# EA08AI-V1.net
KiCad netlist of a schematic drawn in Altium Designer
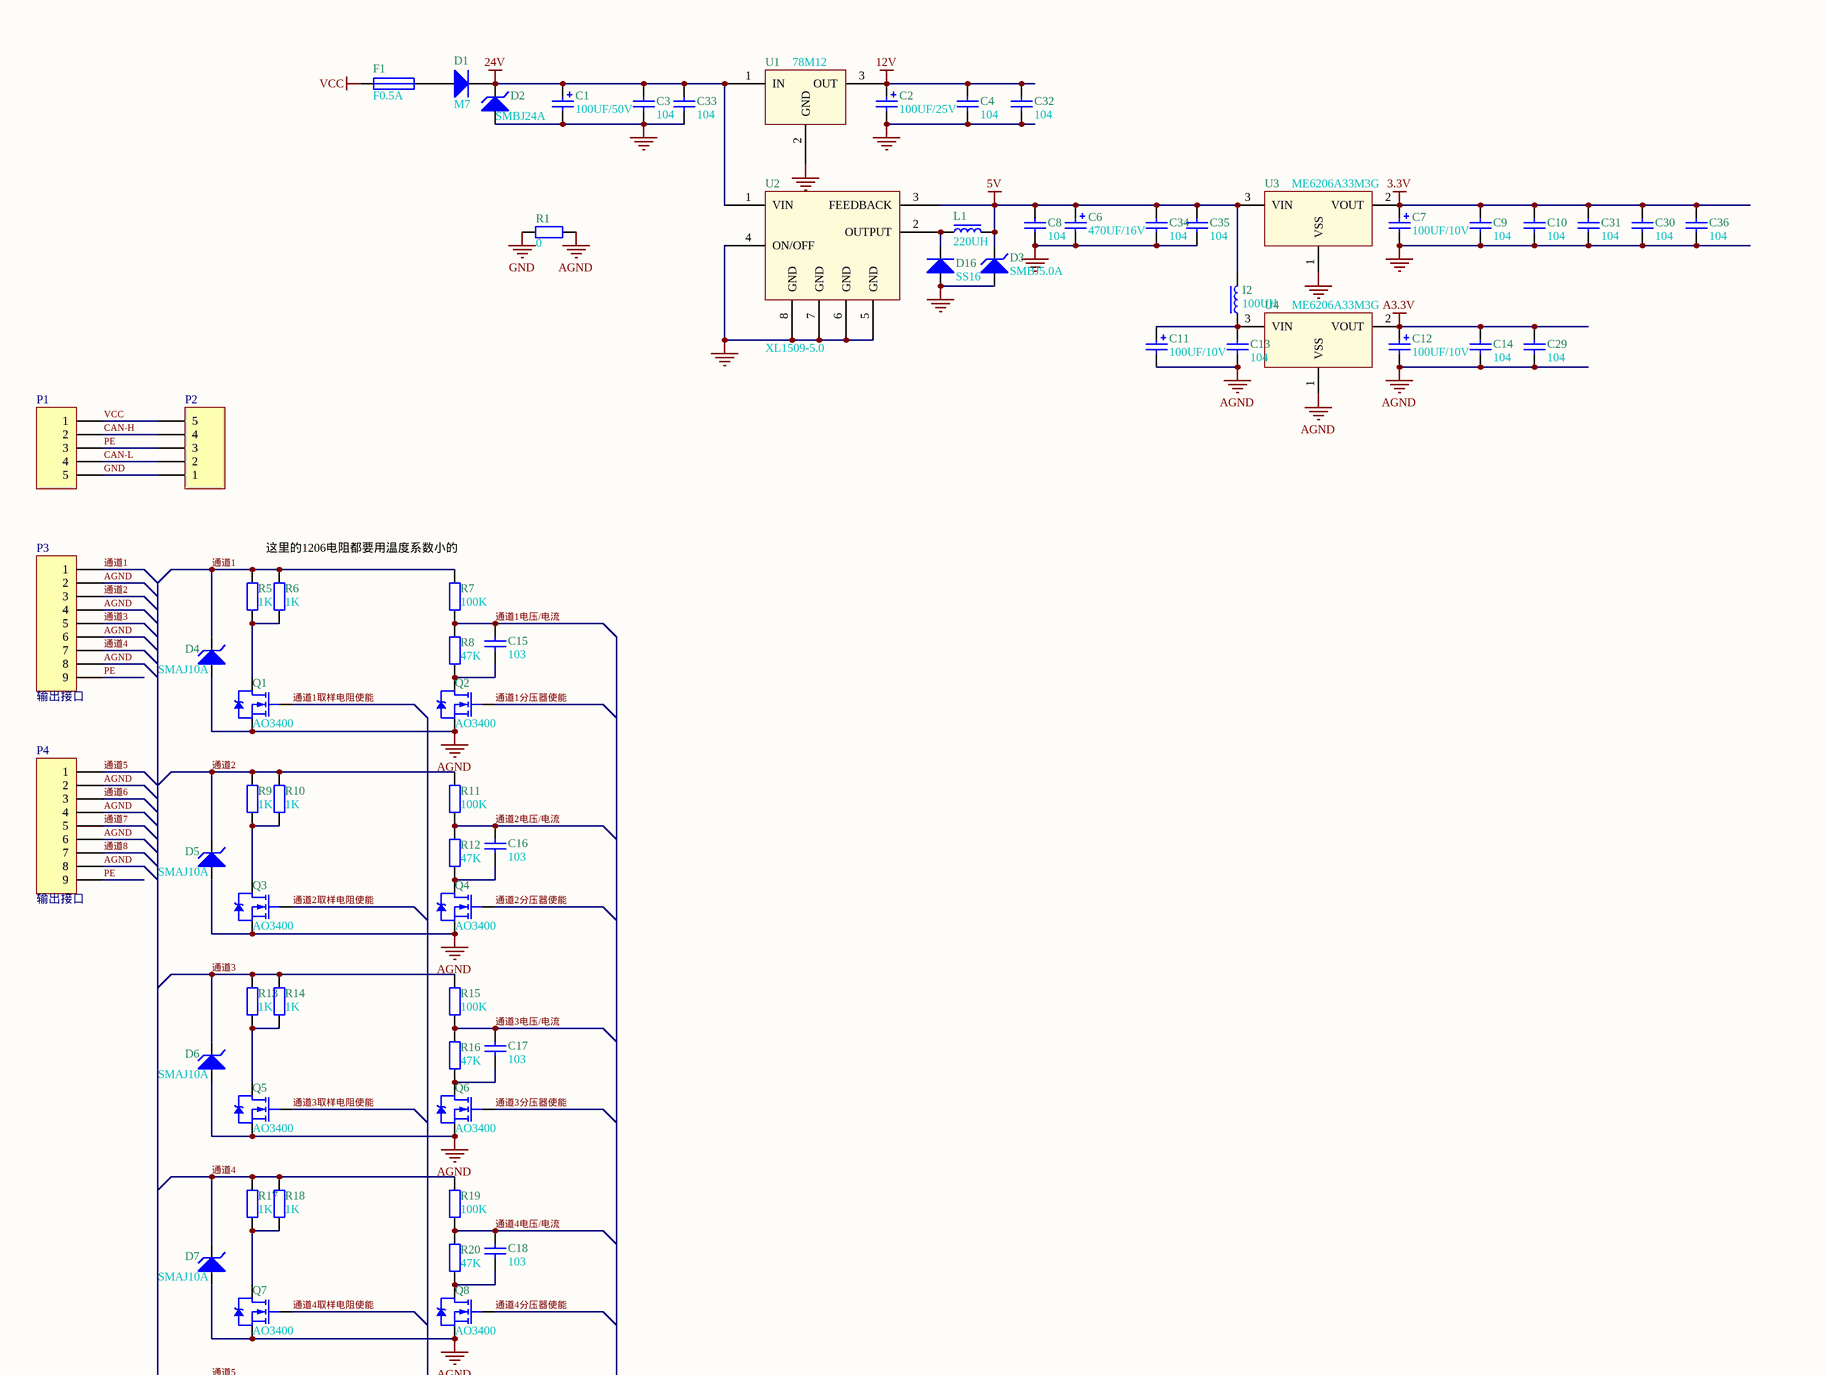
[diagram p0: EA08AI-V1.SchDoc, top]
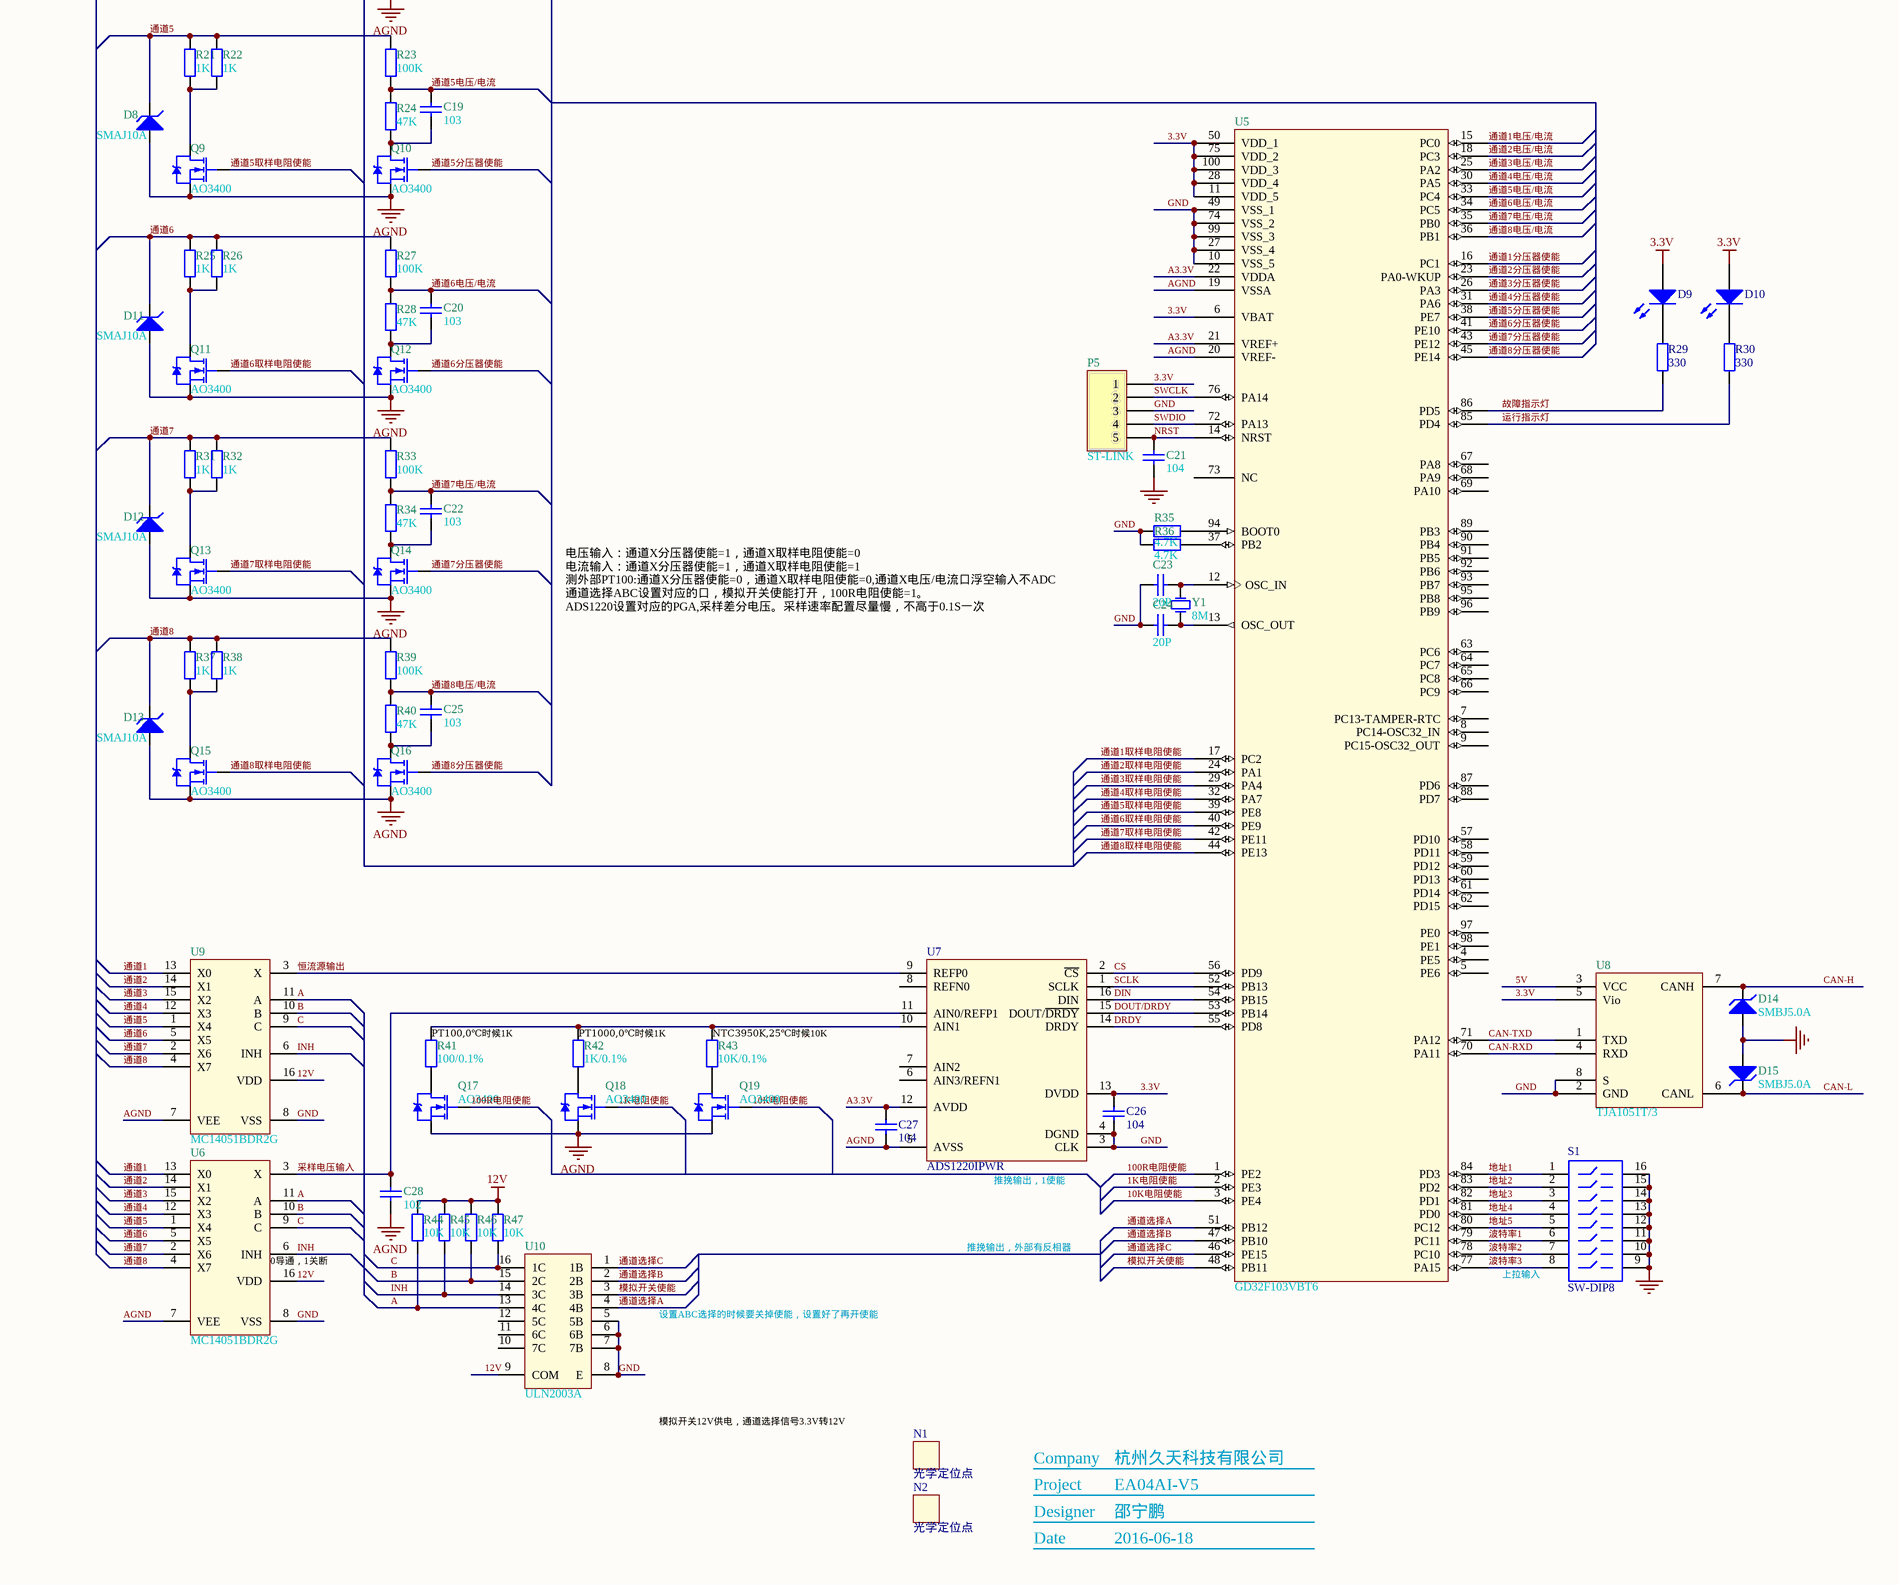
[diagram p1: EA08AI-V1.SchDoc, bottom]

(export (version "E")
  (design (tool "Eeschema 10.0.6"))
  (components
    (comp (ref "C1")
      (value "100UF/50V")
      (footprint "贴片固态电容8*10-M")
      (description "Polarized Capacitor (Radial)")
      (fields (field (name "PUBLISHER") "Altium Limited"))
      (libsource (lib "元件2.0") (part "Cap Pol1"))
    )
    (comp (ref "C2")
      (value "100UF/25V")
      (footprint "贴片固态电容5*5.3")
      (description "Polarized Capacitor (Radial)")
      (fields (field (name "PUBLISHER") "Altium Limited"))
      (libsource (lib "元件2.0") (part "Cap Pol1"))
    )
    (comp (ref "C3")
      (value "104")
      (footprint "C-0603")
      (description "Capacitor")
      (fields (field (name "PUBLISHER") "Altium Limited"))
      (libsource (lib "元件2.0") (part "Cap"))
    )
    (comp (ref "C4")
      (value "104")
      (footprint "C-0603")
      (description "Capacitor")
      (fields (field (name "PUBLISHER") "Altium Limited"))
      (libsource (lib "元件2.0") (part "Cap"))
    )
    (comp (ref "C6")
      (value "470UF/16V")
      (footprint "贴片固态电容8*10-M")
      (description "Polarized Capacitor (Radial)")
      (fields (field (name "PUBLISHER") "Altium Limited"))
      (libsource (lib "元件2.0") (part "Cap Pol1"))
    )
    (comp (ref "C7")
      (value "100UF/10V")
      (footprint "贴片固态电容5*5.3")
      (description "Polarized Capacitor (Radial)")
      (fields (field (name "PUBLISHER") "Altium Limited"))
      (libsource (lib "元件2.0") (part "Cap Pol1"))
    )
    (comp (ref "C8")
      (value "104")
      (footprint "C-0603")
      (description "Capacitor")
      (fields (field (name "PUBLISHER") "Altium Limited"))
      (libsource (lib "元件2.0") (part "Cap"))
    )
    (comp (ref "C9")
      (value "104")
      (footprint "C-0603")
      (description "Capacitor")
      (fields (field (name "PUBLISHER") "Altium Limited"))
      (libsource (lib "元件2.0") (part "Cap"))
    )
    (comp (ref "C10")
      (value "104")
      (footprint "C-0603")
      (description "Capacitor")
      (fields (field (name "PUBLISHER") "Altium Limited"))
      (libsource (lib "元件2.0") (part "Cap"))
    )
    (comp (ref "C11")
      (value "100UF/10V")
      (footprint "贴片固态电容5*5.3")
      (description "Polarized Capacitor (Radial)")
      (fields (field (name "PUBLISHER") "Altium Limited"))
      (libsource (lib "元件2.0") (part "Cap Pol1"))
    )
    (comp (ref "C12")
      (value "100UF/10V")
      (footprint "贴片固态电容5*5.3")
      (description "Polarized Capacitor (Radial)")
      (fields (field (name "PUBLISHER") "Altium Limited"))
      (libsource (lib "元件2.0") (part "Cap Pol1"))
    )
    (comp (ref "C13")
      (value "104")
      (footprint "C-0603")
      (description "Capacitor")
      (fields (field (name "PUBLISHER") "Altium Limited"))
      (libsource (lib "元件2.0") (part "Cap"))
    )
    (comp (ref "C14")
      (value "104")
      (footprint "C-0603")
      (description "Capacitor")
      (fields (field (name "PUBLISHER") "Altium Limited"))
      (libsource (lib "元件2.0") (part "Cap"))
    )
    (comp (ref "C15")
      (value "103")
      (footprint "C-0603")
      (description "0805")
      (fields (field (name "PUBLISHER") "Altium Limited"))
      (libsource (lib "2电容-V1.0") (part "Cap-0603"))
    )
    (comp (ref "C16")
      (value "103")
      (footprint "C-0603")
      (description "0805")
      (fields (field (name "PUBLISHER") "Altium Limited"))
      (libsource (lib "2电容-V1.0") (part "Cap-0603"))
    )
    (comp (ref "C17")
      (value "103")
      (footprint "C-0603")
      (description "0805")
      (fields (field (name "PUBLISHER") "Altium Limited"))
      (libsource (lib "2电容-V1.0") (part "Cap-0603"))
    )
    (comp (ref "C18")
      (value "103")
      (footprint "C-0603")
      (description "0805")
      (fields (field (name "PUBLISHER") "Altium Limited"))
      (libsource (lib "2电容-V1.0") (part "Cap-0603"))
    )
    (comp (ref "C19")
      (value "103")
      (footprint "C-0603")
      (description "0805")
      (fields (field (name "PUBLISHER") "Altium Limited"))
      (libsource (lib "2电容-V1.0") (part "Cap-0603"))
    )
    (comp (ref "C20")
      (value "103")
      (footprint "C-0603")
      (description "0805")
      (fields (field (name "PUBLISHER") "Altium Limited"))
      (libsource (lib "2电容-V1.0") (part "Cap-0603"))
    )
    (comp (ref "C21")
      (value "104")
      (footprint "C-0603")
      (description "Capacitor")
      (fields (field (name "PUBLISHER") "Altium Limited"))
      (libsource (lib "元件2.0") (part "Cap"))
    )
    (comp (ref "C22")
      (value "103")
      (footprint "C-0603")
      (description "0805")
      (fields (field (name "PUBLISHER") "Altium Limited"))
      (libsource (lib "2电容-V1.0") (part "Cap-0603"))
    )
    (comp (ref "C23")
      (value "20P")
      (footprint "C-0603")
      (description "0805")
      (fields (field (name "PUBLISHER") "Altium Limited"))
      (libsource (lib "2电容-V1.0") (part "Cap-0603"))
    )
    (comp (ref "C24")
      (value "20P")
      (footprint "C-0603")
      (description "0805")
      (fields (field (name "PUBLISHER") "Altium Limited"))
      (libsource (lib "2电容-V1.0") (part "Cap-0603"))
    )
    (comp (ref "C25")
      (value "103")
      (footprint "C-0603")
      (description "0805")
      (fields (field (name "PUBLISHER") "Altium Limited"))
      (libsource (lib "2电容-V1.0") (part "Cap-0603"))
    )
    (comp (ref "C26")
      (value "104")
      (footprint "C-0603")
      (description "0805")
      (fields (field (name "PUBLISHER") "Altium Limited"))
      (libsource (lib "2电容-V1.0") (part "Cap-0603"))
    )
    (comp (ref "C27")
      (value "104")
      (footprint "C-0603")
      (description "0805")
      (fields (field (name "PUBLISHER") "Altium Limited"))
      (libsource (lib "2电容-V1.0") (part "Cap-0603"))
    )
    (comp (ref "C28")
      (value "102")
      (footprint "C-0603")
      (description "Capacitor")
      (fields (field (name "PUBLISHER") "Altium Limited"))
      (libsource (lib "元件2.0") (part "Cap"))
    )
    (comp (ref "C29")
      (value "104")
      (footprint "C-0603")
      (description "Capacitor")
      (fields (field (name "PUBLISHER") "Altium Limited"))
      (libsource (lib "元件2.0") (part "Cap"))
    )
    (comp (ref "C30")
      (value "104")
      (footprint "C-0603")
      (description "Capacitor")
      (fields (field (name "PUBLISHER") "Altium Limited"))
      (libsource (lib "元件2.0") (part "Cap"))
    )
    (comp (ref "C31")
      (value "104")
      (footprint "C-0603")
      (description "Capacitor")
      (fields (field (name "PUBLISHER") "Altium Limited"))
      (libsource (lib "元件2.0") (part "Cap"))
    )
    (comp (ref "C32")
      (value "104")
      (footprint "C-0603")
      (description "Capacitor")
      (fields (field (name "PUBLISHER") "Altium Limited"))
      (libsource (lib "元件2.0") (part "Cap"))
    )
    (comp (ref "C33")
      (value "104")
      (footprint "C-0603")
      (description "Capacitor")
      (fields (field (name "PUBLISHER") "Altium Limited"))
      (libsource (lib "元件2.0") (part "Cap"))
    )
    (comp (ref "C34")
      (value "104")
      (footprint "C-0603")
      (description "Capacitor")
      (fields (field (name "PUBLISHER") "Altium Limited"))
      (libsource (lib "元件2.0") (part "Cap"))
    )
    (comp (ref "C35")
      (value "104")
      (footprint "C-0603")
      (description "Capacitor")
      (fields (field (name "PUBLISHER") "Altium Limited"))
      (libsource (lib "元件2.0") (part "Cap"))
    )
    (comp (ref "C36")
      (value "104")
      (footprint "C-0603")
      (description "Capacitor")
      (fields (field (name "PUBLISHER") "Altium Limited"))
      (libsource (lib "元件2.0") (part "Cap"))
    )
    (comp (ref "D1")
      (value "M7")
      (footprint "SMA")
      (description "SMA")
      (fields (field (name "PUBLISHER") "Altium Limited"))
      (libsource (lib "4二极管-V1.1") (part "M7"))
    )
    (comp (ref "D2")
      (value "SMBJ24A")
      (footprint "SMB")
      (description "SMB")
      (libsource (lib "4二极管-V1.1") (part "TVS-1"))
    )
    (comp (ref "D3")
      (value "SMBJ5.0A")
      (footprint "SMB")
      (description "SMB")
      (libsource (lib "4二极管-V1.1") (part "TVS-1"))
    )
    (comp (ref "D4")
      (value "SMAJ10A")
      (footprint "SMA")
      (description "SMB")
      (libsource (lib "4二极管-V1.1") (part "TVS-1"))
    )
    (comp (ref "D5")
      (value "SMAJ10A")
      (footprint "SMA")
      (description "SMB")
      (libsource (lib "4二极管-V1.1") (part "TVS-1"))
    )
    (comp (ref "D6")
      (value "SMAJ10A")
      (footprint "SMA")
      (description "SMB")
      (libsource (lib "4二极管-V1.1") (part "TVS-1"))
    )
    (comp (ref "D7")
      (value "SMAJ10A")
      (footprint "SMA")
      (description "SMB")
      (libsource (lib "4二极管-V1.1") (part "TVS-1"))
    )
    (comp (ref "D8")
      (value "SMAJ10A")
      (footprint "SMA")
      (description "SMB")
      (libsource (lib "4二极管-V1.1") (part "TVS-1"))
    )
    (comp (ref "D9")
      (value "~")
      (footprint "LED Φ3红2.54mm")
      (fields (field (name "PUBLISHER") "Altium Limited"))
      (libsource (lib "4二极管-V1.1") (part "LED-0603-Blue"))
    )
    (comp (ref "D10")
      (value "~")
      (footprint "LED Φ3绿2.54mm")
      (fields (field (name "PUBLISHER") "Altium Limited"))
      (libsource (lib "4二极管-V1.1") (part "LED-0603-Blue"))
    )
    (comp (ref "D11")
      (value "SMAJ10A")
      (footprint "SMA")
      (description "SMB")
      (libsource (lib "4二极管-V1.1") (part "TVS-1"))
    )
    (comp (ref "D12")
      (value "SMAJ10A")
      (footprint "SMA")
      (description "SMB")
      (libsource (lib "4二极管-V1.1") (part "TVS-1"))
    )
    (comp (ref "D13")
      (value "SMAJ10A")
      (footprint "SMA")
      (description "SMB")
      (libsource (lib "4二极管-V1.1") (part "TVS-1"))
    )
    (comp (ref "D14")
      (value "SMBJ5.0A")
      (footprint "SMB")
      (description "SMB")
      (libsource (lib "4二极管-V1.1") (part "TVS-1"))
    )
    (comp (ref "D15")
      (value "SMBJ5.0A")
      (footprint "SMB")
      (description "SMB")
      (libsource (lib "4二极管-V1.1") (part "TVS-1"))
    )
    (comp (ref "D16")
      (value "SS16")
      (footprint "SMA")
      (description "SMA")
      (libsource (lib "4二极管-V1.1") (part "SS14"))
    )
    (comp (ref "F1")
      (value "F0.5A")
      (footprint "FUSE-1808")
      (description "Fuse")
      (fields (field (name "PUBLISHER") "Altium Limited"))
      (libsource (lib "11其他元件-V1.0") (part "Fuse 1"))
    )
    (comp (ref "I2") (value "100UH") (footprint "CD54") (libsource (lib "3电感-V1.0") (part "Inductance3")))
    (comp (ref "L1") (value "220UH") (footprint "CD75") (libsource (lib "3电感-V1.0") (part "Inductance3")))
    (comp (ref "N1") (value "光学定位点") (footprint "MARK-1mm-3mm") (libsource (lib "11其他元件-V1.0") (part "无引脚")))
    (comp (ref "N2") (value "光学定位点") (footprint "MARK-1mm-3mm") (libsource (lib "11其他元件-V1.0") (part "无引脚")))
    (comp (ref "P1")
      (value "~")
      (footprint "弯针5.08-M-5P")
      (description "Header, 5-Pin")
      (fields (field (name "PUBLISHER") "Altium Limited"))
      (libsource (lib "5排针-V1.0") (part "Header 5"))
    )
    (comp (ref "P2")
      (value "~")
      (footprint "KF2EDGVC-5.08-5P弯针")
      (description "Header, 5-Pin")
      (fields (field (name "PUBLISHER") "Altium Limited"))
      (libsource (lib "") (part "Header 5_1"))
    )
    (comp (ref "P3")
      (value "输出接口")
      (footprint "KF2EDGVC-5.08-9P")
      (description "Header, 9-Pin")
      (fields (field (name "PUBLISHER") "Altium Limited"))
      (libsource (lib "5排针-V1.0") (part "Header 9"))
    )
    (comp (ref "P4")
      (value "输出接口")
      (footprint "KF2EDGVC-5.08-9P")
      (description "Header, 9-Pin")
      (fields (field (name "PUBLISHER") "Altium Limited"))
      (libsource (lib "5排针-V1.0") (part "Header 9"))
    )
    (comp (ref "P5")
      (value "ST-LINK")
      (footprint "5P下载口")
      (description "Header, 5-Pin")
      (fields (field (name "PUBLISHER") "Altium Limited"))
      (libsource (lib "5排针-V1.0") (part "Header 5"))
    )
    (comp (ref "Q1")
      (value "AO3400")
      (footprint "SOT-23")
      (description "SOT-23")
      (libsource (lib "4二极管-V1.1") (part "AO3400"))
    )
    (comp (ref "Q2")
      (value "AO3400")
      (footprint "SOT-23")
      (description "SOT-23")
      (libsource (lib "4二极管-V1.1") (part "AO3400"))
    )
    (comp (ref "Q3")
      (value "AO3400")
      (footprint "SOT-23")
      (description "SOT-23")
      (libsource (lib "4二极管-V1.1") (part "AO3400"))
    )
    (comp (ref "Q4")
      (value "AO3400")
      (footprint "SOT-23")
      (description "SOT-23")
      (libsource (lib "4二极管-V1.1") (part "AO3400"))
    )
    (comp (ref "Q5")
      (value "AO3400")
      (footprint "SOT-23")
      (description "SOT-23")
      (libsource (lib "4二极管-V1.1") (part "AO3400"))
    )
    (comp (ref "Q6")
      (value "AO3400")
      (footprint "SOT-23")
      (description "SOT-23")
      (libsource (lib "4二极管-V1.1") (part "AO3400"))
    )
    (comp (ref "Q7")
      (value "AO3400")
      (footprint "SOT-23")
      (description "SOT-23")
      (libsource (lib "4二极管-V1.1") (part "AO3400"))
    )
    (comp (ref "Q8")
      (value "AO3400")
      (footprint "SOT-23")
      (description "SOT-23")
      (libsource (lib "4二极管-V1.1") (part "AO3400"))
    )
    (comp (ref "Q9")
      (value "AO3400")
      (footprint "SOT-23")
      (description "SOT-23")
      (libsource (lib "4二极管-V1.1") (part "AO3400"))
    )
    (comp (ref "Q10")
      (value "AO3400")
      (footprint "SOT-23")
      (description "SOT-23")
      (libsource (lib "4二极管-V1.1") (part "AO3400"))
    )
    (comp (ref "Q11")
      (value "AO3400")
      (footprint "SOT-23")
      (description "SOT-23")
      (libsource (lib "4二极管-V1.1") (part "AO3400"))
    )
    (comp (ref "Q12")
      (value "AO3400")
      (footprint "SOT-23")
      (description "SOT-23")
      (libsource (lib "4二极管-V1.1") (part "AO3400"))
    )
    (comp (ref "Q13")
      (value "AO3400")
      (footprint "SOT-23")
      (description "SOT-23")
      (libsource (lib "4二极管-V1.1") (part "AO3400"))
    )
    (comp (ref "Q14")
      (value "AO3400")
      (footprint "SOT-23")
      (description "SOT-23")
      (libsource (lib "4二极管-V1.1") (part "AO3400"))
    )
    (comp (ref "Q15")
      (value "AO3400")
      (footprint "SOT-23")
      (description "SOT-23")
      (libsource (lib "4二极管-V1.1") (part "AO3400"))
    )
    (comp (ref "Q16")
      (value "AO3400")
      (footprint "SOT-23")
      (description "SOT-23")
      (libsource (lib "4二极管-V1.1") (part "AO3400"))
    )
    (comp (ref "Q17")
      (value "AO3400")
      (footprint "SOT-23")
      (description "SOT-23")
      (libsource (lib "4二极管-V1.1") (part "AO3400"))
    )
    (comp (ref "Q18")
      (value "AO3400")
      (footprint "SOT-23")
      (description "SOT-23")
      (libsource (lib "4二极管-V1.1") (part "AO3400"))
    )
    (comp (ref "Q19")
      (value "AO3400")
      (footprint "SOT-23")
      (description "SOT-23")
      (libsource (lib "4二极管-V1.1") (part "AO3400"))
    )
    (comp (ref "R1")
      (value "0")
      (footprint "R-1206")
      (description "0603")
      (fields (field (name "PUBLISHER") "Altium Limited"))
      (libsource (lib "") (part "Res2-0603_1"))
    )
    (comp (ref "R5")
      (value "1K")
      (footprint "R-1206")
      (description "0603")
      (fields (field (name "PUBLISHER") "Altium Limited"))
      (libsource (lib "") (part "Res2-0603_1"))
    )
    (comp (ref "R6")
      (value "1K")
      (footprint "R-1206")
      (description "0603")
      (fields (field (name "PUBLISHER") "Altium Limited"))
      (libsource (lib "") (part "Res2-0603_1"))
    )
    (comp (ref "R7")
      (value "100K")
      (footprint "R-1206")
      (description "0603")
      (fields (field (name "PUBLISHER") "Altium Limited"))
      (libsource (lib "") (part "Res2-0603_1"))
    )
    (comp (ref "R8")
      (value "47K")
      (footprint "R-1206")
      (description "0603")
      (fields (field (name "PUBLISHER") "Altium Limited"))
      (libsource (lib "") (part "Res2-0603_1"))
    )
    (comp (ref "R9")
      (value "1K")
      (footprint "R-1206")
      (description "0603")
      (fields (field (name "PUBLISHER") "Altium Limited"))
      (libsource (lib "") (part "Res2-0603_1"))
    )
    (comp (ref "R10")
      (value "1K")
      (footprint "R-1206")
      (description "0603")
      (fields (field (name "PUBLISHER") "Altium Limited"))
      (libsource (lib "") (part "Res2-0603_1"))
    )
    (comp (ref "R11")
      (value "100K")
      (footprint "R-1206")
      (description "0603")
      (fields (field (name "PUBLISHER") "Altium Limited"))
      (libsource (lib "") (part "Res2-0603_1"))
    )
    (comp (ref "R12")
      (value "47K")
      (footprint "R-1206")
      (description "0603")
      (fields (field (name "PUBLISHER") "Altium Limited"))
      (libsource (lib "") (part "Res2-0603_1"))
    )
    (comp (ref "R13")
      (value "1K")
      (footprint "R-1206")
      (description "0603")
      (fields (field (name "PUBLISHER") "Altium Limited"))
      (libsource (lib "") (part "Res2-0603_1"))
    )
    (comp (ref "R14")
      (value "1K")
      (footprint "R-1206")
      (description "0603")
      (fields (field (name "PUBLISHER") "Altium Limited"))
      (libsource (lib "") (part "Res2-0603_1"))
    )
    (comp (ref "R15")
      (value "100K")
      (footprint "R-1206")
      (description "0603")
      (fields (field (name "PUBLISHER") "Altium Limited"))
      (libsource (lib "") (part "Res2-0603_1"))
    )
    (comp (ref "R16")
      (value "47K")
      (footprint "R-1206")
      (description "0603")
      (fields (field (name "PUBLISHER") "Altium Limited"))
      (libsource (lib "") (part "Res2-0603_1"))
    )
    (comp (ref "R17")
      (value "1K")
      (footprint "R-1206")
      (description "0603")
      (fields (field (name "PUBLISHER") "Altium Limited"))
      (libsource (lib "") (part "Res2-0603_1"))
    )
    (comp (ref "R18")
      (value "1K")
      (footprint "R-1206")
      (description "0603")
      (fields (field (name "PUBLISHER") "Altium Limited"))
      (libsource (lib "") (part "Res2-0603_1"))
    )
    (comp (ref "R19")
      (value "100K")
      (footprint "R-1206")
      (description "0603")
      (fields (field (name "PUBLISHER") "Altium Limited"))
      (libsource (lib "") (part "Res2-0603_1"))
    )
    (comp (ref "R20")
      (value "47K")
      (footprint "R-1206")
      (description "0603")
      (fields (field (name "PUBLISHER") "Altium Limited"))
      (libsource (lib "") (part "Res2-0603_1"))
    )
    (comp (ref "R21")
      (value "1K")
      (footprint "R-1206")
      (description "0603")
      (fields (field (name "PUBLISHER") "Altium Limited"))
      (libsource (lib "") (part "Res2-0603_1"))
    )
    (comp (ref "R22")
      (value "1K")
      (footprint "R-1206")
      (description "0603")
      (fields (field (name "PUBLISHER") "Altium Limited"))
      (libsource (lib "") (part "Res2-0603_1"))
    )
    (comp (ref "R23")
      (value "100K")
      (footprint "R-1206")
      (description "0603")
      (fields (field (name "PUBLISHER") "Altium Limited"))
      (libsource (lib "") (part "Res2-0603_1"))
    )
    (comp (ref "R24")
      (value "47K")
      (footprint "R-1206")
      (description "0603")
      (fields (field (name "PUBLISHER") "Altium Limited"))
      (libsource (lib "") (part "Res2-0603_1"))
    )
    (comp (ref "R25")
      (value "1K")
      (footprint "R-1206")
      (description "0603")
      (fields (field (name "PUBLISHER") "Altium Limited"))
      (libsource (lib "") (part "Res2-0603_1"))
    )
    (comp (ref "R26")
      (value "1K")
      (footprint "R-1206")
      (description "0603")
      (fields (field (name "PUBLISHER") "Altium Limited"))
      (libsource (lib "") (part "Res2-0603_1"))
    )
    (comp (ref "R27")
      (value "100K")
      (footprint "R-1206")
      (description "0603")
      (fields (field (name "PUBLISHER") "Altium Limited"))
      (libsource (lib "") (part "Res2-0603_1"))
    )
    (comp (ref "R28")
      (value "47K")
      (footprint "R-1206")
      (description "0603")
      (fields (field (name "PUBLISHER") "Altium Limited"))
      (libsource (lib "") (part "Res2-0603_1"))
    )
    (comp (ref "R29")
      (value "330")
      (footprint "R-0603")
      (description "0603")
      (fields (field (name "PUBLISHER") "Altium Limited"))
      (libsource (lib "1电阻-V1.0") (part "Res2-0603"))
    )
    (comp (ref "R30")
      (value "330")
      (footprint "R-0603")
      (description "0603")
      (fields (field (name "PUBLISHER") "Altium Limited"))
      (libsource (lib "1电阻-V1.0") (part "Res2-0603"))
    )
    (comp (ref "R31")
      (value "1K")
      (footprint "R-1206")
      (description "0603")
      (fields (field (name "PUBLISHER") "Altium Limited"))
      (libsource (lib "") (part "Res2-0603_1"))
    )
    (comp (ref "R32")
      (value "1K")
      (footprint "R-1206")
      (description "0603")
      (fields (field (name "PUBLISHER") "Altium Limited"))
      (libsource (lib "") (part "Res2-0603_1"))
    )
    (comp (ref "R33")
      (value "100K")
      (footprint "R-1206")
      (description "0603")
      (fields (field (name "PUBLISHER") "Altium Limited"))
      (libsource (lib "") (part "Res2-0603_1"))
    )
    (comp (ref "R34")
      (value "47K")
      (footprint "R-1206")
      (description "0603")
      (fields (field (name "PUBLISHER") "Altium Limited"))
      (libsource (lib "") (part "Res2-0603_1"))
    )
    (comp (ref "R35")
      (value "4.7K")
      (footprint "R-0603")
      (description "0603")
      (fields (field (name "PUBLISHER") "Altium Limited"))
      (libsource (lib "") (part "Res2-0603_2"))
    )
    (comp (ref "R36")
      (value "4.7K")
      (footprint "R-0603")
      (description "0603")
      (fields (field (name "PUBLISHER") "Altium Limited"))
      (libsource (lib "") (part "Res2-0603_2"))
    )
    (comp (ref "R37")
      (value "1K")
      (footprint "R-1206")
      (description "0603")
      (fields (field (name "PUBLISHER") "Altium Limited"))
      (libsource (lib "") (part "Res2-0603_1"))
    )
    (comp (ref "R38")
      (value "1K")
      (footprint "R-1206")
      (description "0603")
      (fields (field (name "PUBLISHER") "Altium Limited"))
      (libsource (lib "") (part "Res2-0603_1"))
    )
    (comp (ref "R39")
      (value "100K")
      (footprint "R-1206")
      (description "0603")
      (fields (field (name "PUBLISHER") "Altium Limited"))
      (libsource (lib "") (part "Res2-0603_1"))
    )
    (comp (ref "R40")
      (value "47K")
      (footprint "R-1206")
      (description "0603")
      (fields (field (name "PUBLISHER") "Altium Limited"))
      (libsource (lib "") (part "Res2-0603_1"))
    )
    (comp (ref "R41")
      (value "100/0.1%")
      (footprint "R-1206")
      (description "0603")
      (fields (field (name "PUBLISHER") "Altium Limited"))
      (libsource (lib "") (part "Res2-0603_1"))
    )
    (comp (ref "R42")
      (value "1K/0.1%")
      (footprint "R-1206")
      (description "0603")
      (fields (field (name "PUBLISHER") "Altium Limited"))
      (libsource (lib "") (part "Res2-0603_1"))
    )
    (comp (ref "R43")
      (value "10K/0.1%")
      (footprint "R-1206")
      (description "0603")
      (fields (field (name "PUBLISHER") "Altium Limited"))
      (libsource (lib "") (part "Res2-0603_1"))
    )
    (comp (ref "R44")
      (value "10K")
      (footprint "R-0603")
      (description "0603")
      (fields (field (name "PUBLISHER") "Altium Limited"))
      (libsource (lib "1电阻-V1.0") (part "Res2-0603"))
    )
    (comp (ref "R45")
      (value "10K")
      (footprint "R-0603")
      (description "0603")
      (fields (field (name "PUBLISHER") "Altium Limited"))
      (libsource (lib "1电阻-V1.0") (part "Res2-0603"))
    )
    (comp (ref "R46")
      (value "10K")
      (footprint "R-0603")
      (description "0603")
      (fields (field (name "PUBLISHER") "Altium Limited"))
      (libsource (lib "1电阻-V1.0") (part "Res2-0603"))
    )
    (comp (ref "R47")
      (value "10K")
      (footprint "R-0603")
      (description "0603")
      (fields (field (name "PUBLISHER") "Altium Limited"))
      (libsource (lib "1电阻-V1.0") (part "Res2-0603"))
    )
    (comp (ref "S1")
      (value "SW-DIP8")
      (footprint "SW-蓝色拨码开关8P-加高")
      (fields (field (name "PUBLISHER") "Altium Limited"))
      (libsource (lib "开关-V1") (part "SW-DIP8"))
    )
    (comp (ref "U1")
      (value "78M12")
      (footprint "TO-252")
      (description "TO-252")
      (libsource (lib "电源芯片-线性稳压-V1") (part "78M05"))
    )
    (comp (ref "U2")
      (value "XL1509-5.0")
      (footprint "SOP-8-m")
      (description "开关电源 SOP-8")
      (libsource (lib "8集成电路-V1.1") (part "XL1509-ADJ"))
    )
    (comp (ref "U3")
      (value "ME6206A33M3G")
      (footprint "SOT-23")
      (description "LDO稳压 SOT-23")
      (libsource (lib "电源芯片-线性稳压-V1") (part "ME6206A33M3G"))
    )
    (comp (ref "U4")
      (value "ME6206A33M3G")
      (footprint "SOT-23")
      (description "LDO稳压 SOT-23")
      (libsource (lib "电源芯片-线性稳压-V1") (part "ME6206A33M3G"))
    )
    (comp (ref "U5")
      (value "GD32F103VBT6")
      (footprint "LQFP100")
      (libsource (lib "9单片机-V1.0") (part "GD32F103V"))
    )
    (comp (ref "U6")
      (value "MC14051BDR2G")
      (footprint "SOP-16-M")
      (libsource (lib "模拟开关") (part "MC14051BDR2G"))
    )
    (comp (ref "U7")
      (value "ADS1220IPWR")
      (footprint "TSSOP-16")
      (description "24位四通道ADC")
      (libsource (lib "ADC-DAC-V1") (part "ADS1220IPWR"))
    )
    (comp (ref "U8") (value "TJA1051T/3") (footprint "SOP-8-m") (libsource (lib "通讯-V1") (part "TJA1051T/3")))
    (comp (ref "U9")
      (value "MC14051BDR2G")
      (footprint "SOP-16-M")
      (libsource (lib "模拟开关") (part "MC14051BDR2G"))
    )
    (comp (ref "U10")
      (value "ULN2003A")
      (footprint "SOP-16-M")
      (libsource (lib "8集成电路-V1.1") (part "ULN2003A"))
    )
    (comp (ref "Y1") (value "8M") (footprint "HC-49SMD") (libsource (lib "11其他元件-V1.0") (part "晶振")))
  )
  (nets
    (net (code "1") (name "/1K电阻使能") (class "Default")
      (node (ref "Q18") (pin "1") (pinfunction "G_1") (pintype "passive"))
      (node (ref "U5") (pin "2") (pinfunction "PE3_2") (pintype "bidirectional"))
    )
    (net (code "2") (name "/10K电阻使能") (class "Default")
      (node (ref "Q19") (pin "1") (pinfunction "G_1") (pintype "passive"))
      (node (ref "U5") (pin "3") (pinfunction "PE4_3") (pintype "bidirectional"))
    )
    (net (code "3") (name "/100R电阻使能") (class "Default")
      (node (ref "Q17") (pin "1") (pinfunction "G_1") (pintype "passive"))
      (node (ref "U5") (pin "1") (pinfunction "PE2_1") (pintype "bidirectional"))
    )
    (net (code "4") (name "/A") (class "Default")
      (node (ref "R44") (pin "1") (pinfunction "1_1") (pintype "passive"))
      (node (ref "U10") (pin "13") (pinfunction "4C_13") (pintype "passive"))
      (node (ref "U6") (pin "11") (pinfunction "A_11") (pintype "passive"))
      (node (ref "U9") (pin "11") (pinfunction "A_11") (pintype "passive"))
    )
    (net (code "5") (name "/B") (class "Default")
      (node (ref "R46") (pin "1") (pinfunction "1_1") (pintype "passive"))
      (node (ref "U10") (pin "15") (pinfunction "2C_15") (pintype "passive"))
      (node (ref "U6") (pin "10") (pinfunction "B_10") (pintype "passive"))
      (node (ref "U9") (pin "10") (pinfunction "B_10") (pintype "passive"))
    )
    (net (code "6") (name "/C") (class "Default")
      (node (ref "R47") (pin "1") (pinfunction "1_1") (pintype "passive"))
      (node (ref "U10") (pin "16") (pinfunction "1C_16") (pintype "passive"))
      (node (ref "U6") (pin "9") (pinfunction "C_9") (pintype "passive"))
      (node (ref "U9") (pin "9") (pinfunction "C_9") (pintype "passive"))
    )
    (net (code "7") (name "/CAN-H") (class "Default")
      (node (ref "D14") (pin "2") (pinfunction "K_2") (pintype "passive"))
      (node (ref "P1") (pin "2") (pinfunction "2_2") (pintype "passive"))
      (node (ref "P2") (pin "4") (pinfunction "4_4") (pintype "passive"))
      (node (ref "U8") (pin "7") (pinfunction "CANH_7") (pintype "passive"))
    )
    (net (code "8") (name "/CAN-L") (class "Default")
      (node (ref "D15") (pin "2") (pinfunction "K_2") (pintype "passive"))
      (node (ref "P1") (pin "4") (pinfunction "4_4") (pintype "passive"))
      (node (ref "P2") (pin "2") (pinfunction "2_2") (pintype "passive"))
      (node (ref "U8") (pin "6") (pinfunction "CANL_6") (pintype "passive"))
    )
    (net (code "9") (name "/CAN-RXD") (class "Default")
      (node (ref "U5") (pin "70") (pinfunction "PA11_70") (pintype "bidirectional"))
      (node (ref "U8") (pin "4") (pinfunction "RXD_4") (pintype "passive"))
    )
    (net (code "10") (name "/CAN-TXD") (class "Default")
      (node (ref "U5") (pin "71") (pinfunction "PA12_71") (pintype "bidirectional"))
      (node (ref "U8") (pin "1") (pinfunction "TXD_1") (pintype "passive"))
    )
    (net (code "11") (name "/CS") (class "Default")
      (node (ref "U5") (pin "56") (pinfunction "PD9_56") (pintype "bidirectional"))
      (node (ref "U7") (pin "2") (pinfunction "~{CS}_2") (pintype "passive"))
    )
    (net (code "12") (name "/DIN") (class "Default")
      (node (ref "U5") (pin "54") (pinfunction "PB15_54") (pintype "bidirectional"))
      (node (ref "U7") (pin "16") (pinfunction "DIN_16") (pintype "passive"))
    )
    (net (code "13") (name "/DOUT{slash}DRDY") (class "Default")
      (node (ref "U5") (pin "53") (pinfunction "PB14_53") (pintype "bidirectional"))
      (node (ref "U7") (pin "15") (pinfunction "DOUT/~{DRDY}_15") (pintype "passive"))
    )
    (net (code "14") (name "/DRDY") (class "Default")
      (node (ref "U5") (pin "55") (pinfunction "PD8_55") (pintype "bidirectional"))
      (node (ref "U7") (pin "14") (pinfunction "DRDY_14") (pintype "passive"))
    )
    (net (code "15") (name "/INH") (class "Default")
      (node (ref "R45") (pin "1") (pinfunction "1_1") (pintype "passive"))
      (node (ref "U10") (pin "14") (pinfunction "3C_14") (pintype "passive"))
      (node (ref "U6") (pin "6") (pinfunction "INH_6") (pintype "passive"))
      (node (ref "U9") (pin "6") (pinfunction "INH_6") (pintype "passive"))
    )
    (net (code "16") (name "/NRST") (class "Default")
      (node (ref "C21") (pin "2") (pinfunction "2_2") (pintype "passive"))
      (node (ref "P5") (pin "5") (pinfunction "5_5") (pintype "passive"))
      (node (ref "U5") (pin "14") (pinfunction "NRST_14") (pintype "bidirectional"))
    )
    (net (code "17") (name "/PE") (class "Default")
      (node (ref "P1") (pin "3") (pinfunction "3_3") (pintype "passive"))
      (node (ref "P2") (pin "3") (pinfunction "3_3") (pintype "passive"))
      (node (ref "P3") (pin "9") (pinfunction "9_9") (pintype "passive"))
      (node (ref "P4") (pin "9") (pinfunction "9_9") (pintype "passive"))
    )
    (net (code "18") (name "/SCLK") (class "Default")
      (node (ref "U5") (pin "52") (pinfunction "PB13_52") (pintype "bidirectional"))
      (node (ref "U7") (pin "1") (pinfunction "SCLK_1") (pintype "passive"))
    )
    (net (code "19") (name "/SWCLK") (class "Default")
      (node (ref "P5") (pin "2") (pinfunction "2_2") (pintype "passive"))
      (node (ref "U5") (pin "76") (pinfunction "PA14_76") (pintype "bidirectional"))
    )
    (net (code "20") (name "/SWDIO") (class "Default")
      (node (ref "P5") (pin "4") (pinfunction "4_4") (pintype "passive"))
      (node (ref "U5") (pin "72") (pinfunction "PA13_72") (pintype "bidirectional"))
    )
    (net (code "21") (name "/地址1") (class "Default")
      (node (ref "S1") (pin "1") (pinfunction "1_1") (pintype "passive"))
      (node (ref "U5") (pin "84") (pinfunction "PD3_84") (pintype "bidirectional"))
    )
    (net (code "22") (name "/地址2") (class "Default")
      (node (ref "S1") (pin "2") (pinfunction "2_2") (pintype "passive"))
      (node (ref "U5") (pin "83") (pinfunction "PD2_83") (pintype "bidirectional"))
    )
    (net (code "23") (name "/地址3") (class "Default")
      (node (ref "S1") (pin "3") (pinfunction "3_3") (pintype "passive"))
      (node (ref "U5") (pin "82") (pinfunction "PD1_82") (pintype "bidirectional"))
    )
    (net (code "24") (name "/地址4") (class "Default")
      (node (ref "S1") (pin "4") (pinfunction "4_4") (pintype "passive"))
      (node (ref "U5") (pin "81") (pinfunction "PD0_81") (pintype "bidirectional"))
    )
    (net (code "25") (name "/地址5") (class "Default")
      (node (ref "S1") (pin "5") (pinfunction "5_5") (pintype "passive"))
      (node (ref "U5") (pin "80") (pinfunction "PC12_80") (pintype "bidirectional"))
    )
    (net (code "26") (name "/恒流源输出") (class "Default")
      (node (ref "U7") (pin "9") (pinfunction "REFP0_9") (pintype "passive"))
      (node (ref "U9") (pin "3") (pinfunction "X_3") (pintype "passive"))
    )
    (net (code "27") (name "/故障指示灯") (class "Default")
      (node (ref "R29") (pin "1") (pinfunction "1_1") (pintype "passive"))
      (node (ref "U5") (pin "86") (pinfunction "PD5_86") (pintype "bidirectional"))
    )
    (net (code "28") (name "/模拟开关使能") (class "Default")
      (node (ref "U10") (pin "3") (pinfunction "3B_3") (pintype "passive"))
      (node (ref "U5") (pin "48") (pinfunction "PB11_48") (pintype "bidirectional"))
    )
    (net (code "29") (name "/波特率1") (class "Default")
      (node (ref "S1") (pin "6") (pinfunction "6_6") (pintype "passive"))
      (node (ref "U5") (pin "79") (pinfunction "PC11_79") (pintype "bidirectional"))
    )
    (net (code "30") (name "/波特率2") (class "Default")
      (node (ref "S1") (pin "7") (pinfunction "7_7") (pintype "passive"))
      (node (ref "U5") (pin "78") (pinfunction "PC10_78") (pintype "bidirectional"))
    )
    (net (code "31") (name "/波特率3") (class "Default")
      (node (ref "S1") (pin "8") (pinfunction "8_8") (pintype "passive"))
      (node (ref "U5") (pin "77") (pinfunction "PA15_77") (pintype "bidirectional"))
    )
    (net (code "32") (name "/运行指示灯") (class "Default")
      (node (ref "R30") (pin "1") (pinfunction "1_1") (pintype "passive"))
      (node (ref "U5") (pin "85") (pinfunction "PD4_85") (pintype "bidirectional"))
    )
    (net (code "33") (name "/通道1") (class "Default")
      (node (ref "D4") (pin "2") (pinfunction "K_2") (pintype "passive"))
      (node (ref "P3") (pin "1") (pinfunction "1_1") (pintype "passive"))
      (node (ref "R5") (pin "2") (pinfunction "2_2") (pintype "passive"))
      (node (ref "R6") (pin "2") (pinfunction "2_2") (pintype "passive"))
      (node (ref "R7") (pin "2") (pinfunction "2_2") (pintype "passive"))
      (node (ref "U6") (pin "13") (pinfunction "X0_13") (pintype "passive"))
      (node (ref "U9") (pin "13") (pinfunction "X0_13") (pintype "passive"))
    )
    (net (code "34") (name "/通道1分压器使能") (class "Default")
      (node (ref "Q2") (pin "1") (pinfunction "G_1") (pintype "passive"))
      (node (ref "U5") (pin "16") (pinfunction "PC1_16") (pintype "bidirectional"))
    )
    (net (code "35") (name "/通道1取样电阻使能") (class "Default")
      (node (ref "Q1") (pin "1") (pinfunction "G_1") (pintype "passive"))
      (node (ref "U5") (pin "17") (pinfunction "PC2_17") (pintype "bidirectional"))
    )
    (net (code "36") (name "/通道1电压{slash}电流") (class "Default")
      (node (ref "C15") (pin "2") (pinfunction "2_2") (pintype "passive"))
      (node (ref "R7") (pin "1") (pinfunction "1_1") (pintype "passive"))
      (node (ref "R8") (pin "2") (pinfunction "2_2") (pintype "passive"))
      (node (ref "U5") (pin "15") (pinfunction "PC0_15") (pintype "bidirectional"))
    )
    (net (code "37") (name "/通道2") (class "Default")
      (node (ref "D5") (pin "2") (pinfunction "K_2") (pintype "passive"))
      (node (ref "P3") (pin "3") (pinfunction "3_3") (pintype "passive"))
      (node (ref "R10") (pin "2") (pinfunction "2_2") (pintype "passive"))
      (node (ref "R11") (pin "2") (pinfunction "2_2") (pintype "passive"))
      (node (ref "R9") (pin "2") (pinfunction "2_2") (pintype "passive"))
      (node (ref "U6") (pin "14") (pinfunction "X1_14") (pintype "passive"))
      (node (ref "U9") (pin "14") (pinfunction "X1_14") (pintype "passive"))
    )
    (net (code "38") (name "/通道2分压器使能") (class "Default")
      (node (ref "Q4") (pin "1") (pinfunction "G_1") (pintype "passive"))
      (node (ref "U5") (pin "23") (pinfunction "PA0-WKUP_23") (pintype "bidirectional"))
    )
    (net (code "39") (name "/通道2取样电阻使能") (class "Default")
      (node (ref "Q3") (pin "1") (pinfunction "G_1") (pintype "passive"))
      (node (ref "U5") (pin "24") (pinfunction "PA1_24") (pintype "bidirectional"))
    )
    (net (code "40") (name "/通道2电压{slash}电流") (class "Default")
      (node (ref "C16") (pin "2") (pinfunction "2_2") (pintype "passive"))
      (node (ref "R11") (pin "1") (pinfunction "1_1") (pintype "passive"))
      (node (ref "R12") (pin "2") (pinfunction "2_2") (pintype "passive"))
      (node (ref "U5") (pin "18") (pinfunction "PC3_18") (pintype "bidirectional"))
    )
    (net (code "41") (name "/通道3") (class "Default")
      (node (ref "D6") (pin "2") (pinfunction "K_2") (pintype "passive"))
      (node (ref "P3") (pin "5") (pinfunction "5_5") (pintype "passive"))
      (node (ref "R13") (pin "2") (pinfunction "2_2") (pintype "passive"))
      (node (ref "R14") (pin "2") (pinfunction "2_2") (pintype "passive"))
      (node (ref "R15") (pin "2") (pinfunction "2_2") (pintype "passive"))
      (node (ref "U6") (pin "15") (pinfunction "X2_15") (pintype "passive"))
      (node (ref "U9") (pin "15") (pinfunction "X2_15") (pintype "passive"))
    )
    (net (code "42") (name "/通道3分压器使能") (class "Default")
      (node (ref "Q6") (pin "1") (pinfunction "G_1") (pintype "passive"))
      (node (ref "U5") (pin "26") (pinfunction "PA3_26") (pintype "bidirectional"))
    )
    (net (code "43") (name "/通道3取样电阻使能") (class "Default")
      (node (ref "Q5") (pin "1") (pinfunction "G_1") (pintype "passive"))
      (node (ref "U5") (pin "29") (pinfunction "PA4_29") (pintype "bidirectional"))
    )
    (net (code "44") (name "/通道3电压{slash}电流") (class "Default")
      (node (ref "C17") (pin "2") (pinfunction "2_2") (pintype "passive"))
      (node (ref "R15") (pin "1") (pinfunction "1_1") (pintype "passive"))
      (node (ref "R16") (pin "2") (pinfunction "2_2") (pintype "passive"))
      (node (ref "U5") (pin "25") (pinfunction "PA2_25") (pintype "bidirectional"))
    )
    (net (code "45") (name "/通道4") (class "Default")
      (node (ref "D7") (pin "2") (pinfunction "K_2") (pintype "passive"))
      (node (ref "P3") (pin "7") (pinfunction "7_7") (pintype "passive"))
      (node (ref "R17") (pin "2") (pinfunction "2_2") (pintype "passive"))
      (node (ref "R18") (pin "2") (pinfunction "2_2") (pintype "passive"))
      (node (ref "R19") (pin "2") (pinfunction "2_2") (pintype "passive"))
      (node (ref "U6") (pin "12") (pinfunction "X3_12") (pintype "passive"))
      (node (ref "U9") (pin "12") (pinfunction "X3_12") (pintype "passive"))
    )
    (net (code "46") (name "/通道4分压器使能") (class "Default")
      (node (ref "Q8") (pin "1") (pinfunction "G_1") (pintype "passive"))
      (node (ref "U5") (pin "31") (pinfunction "PA6_31") (pintype "bidirectional"))
    )
    (net (code "47") (name "/通道4取样电阻使能") (class "Default")
      (node (ref "Q7") (pin "1") (pinfunction "G_1") (pintype "passive"))
      (node (ref "U5") (pin "32") (pinfunction "PA7_32") (pintype "bidirectional"))
    )
    (net (code "48") (name "/通道4电压{slash}电流") (class "Default")
      (node (ref "C18") (pin "2") (pinfunction "2_2") (pintype "passive"))
      (node (ref "R19") (pin "1") (pinfunction "1_1") (pintype "passive"))
      (node (ref "R20") (pin "2") (pinfunction "2_2") (pintype "passive"))
      (node (ref "U5") (pin "30") (pinfunction "PA5_30") (pintype "bidirectional"))
    )
    (net (code "49") (name "/通道5") (class "Default")
      (node (ref "D8") (pin "2") (pinfunction "K_2") (pintype "passive"))
      (node (ref "P4") (pin "1") (pinfunction "1_1") (pintype "passive"))
      (node (ref "R21") (pin "2") (pinfunction "2_2") (pintype "passive"))
      (node (ref "R22") (pin "2") (pinfunction "2_2") (pintype "passive"))
      (node (ref "R23") (pin "2") (pinfunction "2_2") (pintype "passive"))
      (node (ref "U6") (pin "1") (pinfunction "X4_1") (pintype "passive"))
      (node (ref "U9") (pin "1") (pinfunction "X4_1") (pintype "passive"))
    )
    (net (code "50") (name "/通道5分压器使能") (class "Default")
      (node (ref "Q10") (pin "1") (pinfunction "G_1") (pintype "passive"))
      (node (ref "U5") (pin "38") (pinfunction "PE7_38") (pintype "bidirectional"))
    )
    (net (code "51") (name "/通道5取样电阻使能") (class "Default")
      (node (ref "Q9") (pin "1") (pinfunction "G_1") (pintype "passive"))
      (node (ref "U5") (pin "39") (pinfunction "PE8_39") (pintype "bidirectional"))
    )
    (net (code "52") (name "/通道5电压{slash}电流") (class "Default")
      (node (ref "C19") (pin "2") (pinfunction "2_2") (pintype "passive"))
      (node (ref "R23") (pin "1") (pinfunction "1_1") (pintype "passive"))
      (node (ref "R24") (pin "2") (pinfunction "2_2") (pintype "passive"))
      (node (ref "U5") (pin "33") (pinfunction "PC4_33") (pintype "bidirectional"))
    )
    (net (code "53") (name "/通道6") (class "Default")
      (node (ref "D11") (pin "2") (pinfunction "K_2") (pintype "passive"))
      (node (ref "P4") (pin "3") (pinfunction "3_3") (pintype "passive"))
      (node (ref "R25") (pin "2") (pinfunction "2_2") (pintype "passive"))
      (node (ref "R26") (pin "2") (pinfunction "2_2") (pintype "passive"))
      (node (ref "R27") (pin "2") (pinfunction "2_2") (pintype "passive"))
      (node (ref "U6") (pin "5") (pinfunction "X5_5") (pintype "passive"))
      (node (ref "U9") (pin "5") (pinfunction "X5_5") (pintype "passive"))
    )
    (net (code "54") (name "/通道6分压器使能") (class "Default")
      (node (ref "Q12") (pin "1") (pinfunction "G_1") (pintype "passive"))
      (node (ref "U5") (pin "41") (pinfunction "PE10_41") (pintype "bidirectional"))
    )
    (net (code "55") (name "/通道6取样电阻使能") (class "Default")
      (node (ref "Q11") (pin "1") (pinfunction "G_1") (pintype "passive"))
      (node (ref "U5") (pin "40") (pinfunction "PE9_40") (pintype "bidirectional"))
    )
    (net (code "56") (name "/通道6电压{slash}电流") (class "Default")
      (node (ref "C20") (pin "2") (pinfunction "2_2") (pintype "passive"))
      (node (ref "R27") (pin "1") (pinfunction "1_1") (pintype "passive"))
      (node (ref "R28") (pin "2") (pinfunction "2_2") (pintype "passive"))
      (node (ref "U5") (pin "34") (pinfunction "PC5_34") (pintype "bidirectional"))
    )
    (net (code "57") (name "/通道7") (class "Default")
      (node (ref "D12") (pin "2") (pinfunction "K_2") (pintype "passive"))
      (node (ref "P4") (pin "5") (pinfunction "5_5") (pintype "passive"))
      (node (ref "R31") (pin "2") (pinfunction "2_2") (pintype "passive"))
      (node (ref "R32") (pin "2") (pinfunction "2_2") (pintype "passive"))
      (node (ref "R33") (pin "2") (pinfunction "2_2") (pintype "passive"))
      (node (ref "U6") (pin "2") (pinfunction "X6_2") (pintype "passive"))
      (node (ref "U9") (pin "2") (pinfunction "X6_2") (pintype "passive"))
    )
    (net (code "58") (name "/通道7分压器使能") (class "Default")
      (node (ref "Q14") (pin "1") (pinfunction "G_1") (pintype "passive"))
      (node (ref "U5") (pin "43") (pinfunction "PE12_43") (pintype "bidirectional"))
    )
    (net (code "59") (name "/通道7取样电阻使能") (class "Default")
      (node (ref "Q13") (pin "1") (pinfunction "G_1") (pintype "passive"))
      (node (ref "U5") (pin "42") (pinfunction "PE11_42") (pintype "bidirectional"))
    )
    (net (code "60") (name "/通道7电压{slash}电流") (class "Default")
      (node (ref "C22") (pin "2") (pinfunction "2_2") (pintype "passive"))
      (node (ref "R33") (pin "1") (pinfunction "1_1") (pintype "passive"))
      (node (ref "R34") (pin "2") (pinfunction "2_2") (pintype "passive"))
      (node (ref "U5") (pin "35") (pinfunction "PB0_35") (pintype "bidirectional"))
    )
    (net (code "61") (name "/通道8") (class "Default")
      (node (ref "D13") (pin "2") (pinfunction "K_2") (pintype "passive"))
      (node (ref "P4") (pin "7") (pinfunction "7_7") (pintype "passive"))
      (node (ref "R37") (pin "2") (pinfunction "2_2") (pintype "passive"))
      (node (ref "R38") (pin "2") (pinfunction "2_2") (pintype "passive"))
      (node (ref "R39") (pin "2") (pinfunction "2_2") (pintype "passive"))
      (node (ref "U6") (pin "4") (pinfunction "X7_4") (pintype "passive"))
      (node (ref "U9") (pin "4") (pinfunction "X7_4") (pintype "passive"))
    )
    (net (code "62") (name "/通道8分压器使能") (class "Default")
      (node (ref "Q16") (pin "1") (pinfunction "G_1") (pintype "passive"))
      (node (ref "U5") (pin "45") (pinfunction "PE14_45") (pintype "bidirectional"))
    )
    (net (code "63") (name "/通道8取样电阻使能") (class "Default")
      (node (ref "Q15") (pin "1") (pinfunction "G_1") (pintype "passive"))
      (node (ref "U5") (pin "44") (pinfunction "PE13_44") (pintype "bidirectional"))
    )
    (net (code "64") (name "/通道8电压{slash}电流") (class "Default")
      (node (ref "C25") (pin "2") (pinfunction "2_2") (pintype "passive"))
      (node (ref "R39") (pin "1") (pinfunction "1_1") (pintype "passive"))
      (node (ref "R40") (pin "2") (pinfunction "2_2") (pintype "passive"))
      (node (ref "U5") (pin "36") (pinfunction "PB1_36") (pintype "bidirectional"))
    )
    (net (code "65") (name "/通道选择A") (class "Default")
      (node (ref "U10") (pin "4") (pinfunction "4B_4") (pintype "passive"))
      (node (ref "U5") (pin "51") (pinfunction "PB12_51") (pintype "bidirectional"))
    )
    (net (code "66") (name "/通道选择B") (class "Default")
      (node (ref "U10") (pin "2") (pinfunction "2B_2") (pintype "passive"))
      (node (ref "U5") (pin "47") (pinfunction "PB10_47") (pintype "bidirectional"))
    )
    (net (code "67") (name "/通道选择C") (class "Default")
      (node (ref "U10") (pin "1") (pinfunction "1B_1") (pintype "passive"))
      (node (ref "U5") (pin "46") (pinfunction "PE15_46") (pintype "bidirectional"))
    )
    (net (code "68") (name "/采样电压输入") (class "Default")
      (node (ref "C28") (pin "2") (pinfunction "2_2") (pintype "passive"))
      (node (ref "U6") (pin "3") (pinfunction "X_3") (pintype "passive"))
      (node (ref "U7") (pin "11") (pinfunction "AIN0/REFP1_11") (pintype "passive"))
    )
    (net (code "69") (name "3.3V") (class "Default")
      (node (ref "C10") (pin "2") (pinfunction "2_2") (pintype "passive"))
      (node (ref "C26") (pin "2") (pinfunction "2_2") (pintype "passive"))
      (node (ref "C30") (pin "2") (pinfunction "2_2") (pintype "passive"))
      (node (ref "C31") (pin "2") (pinfunction "2_2") (pintype "passive"))
      (node (ref "C36") (pin "2") (pinfunction "2_2") (pintype "passive"))
      (node (ref "C7") (pin "1") (pinfunction "1_1") (pintype "passive"))
      (node (ref "C9") (pin "2") (pinfunction "2_2") (pintype "passive"))
      (node (ref "D10") (pin "1") (pinfunction "A_1") (pintype "passive"))
      (node (ref "D9") (pin "1") (pinfunction "A_1") (pintype "passive"))
      (node (ref "P5") (pin "1") (pinfunction "1_1") (pintype "passive"))
      (node (ref "U3") (pin "2") (pinfunction "VOUT_2") (pintype "passive"))
      (node (ref "U5") (pin "100") (pinfunction "VDD_3_100") (pintype "power_in"))
      (node (ref "U5") (pin "11") (pinfunction "VDD_5_11") (pintype "power_in"))
      (node (ref "U5") (pin "28") (pinfunction "VDD_4_28") (pintype "power_in"))
      (node (ref "U5") (pin "50") (pinfunction "VDD_1_50") (pintype "power_in"))
      (node (ref "U5") (pin "6") (pinfunction "VBAT_6") (pintype "power_in"))
      (node (ref "U5") (pin "75") (pinfunction "VDD_2_75") (pintype "power_in"))
      (node (ref "U7") (pin "13") (pinfunction "DVDD_13") (pintype "passive"))
      (node (ref "U8") (pin "5") (pinfunction "Vio_5") (pintype "passive"))
    )
    (net (code "70") (name "5V") (class "Default")
      (node (ref "C34") (pin "2") (pinfunction "2_2") (pintype "passive"))
      (node (ref "C35") (pin "2") (pinfunction "2_2") (pintype "passive"))
      (node (ref "C6") (pin "1") (pinfunction "1_1") (pintype "passive"))
      (node (ref "C8") (pin "2") (pinfunction "2_2") (pintype "passive"))
      (node (ref "D3") (pin "2") (pinfunction "K_2") (pintype "passive"))
      (node (ref "I2") (pin "2") (pinfunction "2_2") (pintype "passive"))
      (node (ref "L1") (pin "2") (pinfunction "2_2") (pintype "passive"))
      (node (ref "U2") (pin "3") (pinfunction "FEEDBACK_3") (pintype "passive"))
      (node (ref "U3") (pin "3") (pinfunction "VIN_3") (pintype "passive"))
      (node (ref "U8") (pin "3") (pinfunction "VCC_3") (pintype "passive"))
    )
    (net (code "71") (name "12V") (class "Default")
      (node (ref "C2") (pin "1") (pinfunction "1_1") (pintype "passive"))
      (node (ref "C32") (pin "2") (pinfunction "2_2") (pintype "passive"))
      (node (ref "C4") (pin "2") (pinfunction "2_2") (pintype "passive"))
      (node (ref "R44") (pin "2") (pinfunction "2_2") (pintype "passive"))
      (node (ref "R45") (pin "2") (pinfunction "2_2") (pintype "passive"))
      (node (ref "R46") (pin "2") (pinfunction "2_2") (pintype "passive"))
      (node (ref "R47") (pin "2") (pinfunction "2_2") (pintype "passive"))
      (node (ref "U1") (pin "3") (pinfunction "OUT_3") (pintype "passive"))
      (node (ref "U10") (pin "9") (pinfunction "COM_9") (pintype "passive"))
      (node (ref "U6") (pin "16") (pinfunction "VDD_16") (pintype "passive"))
      (node (ref "U9") (pin "16") (pinfunction "VDD_16") (pintype "passive"))
    )
    (net (code "72") (name "24V") (class "Default")
      (node (ref "C1") (pin "1") (pinfunction "1_1") (pintype "passive"))
      (node (ref "C3") (pin "2") (pinfunction "2_2") (pintype "passive"))
      (node (ref "C33") (pin "2") (pinfunction "2_2") (pintype "passive"))
      (node (ref "D1") (pin "2") (pinfunction "K_2") (pintype "passive"))
      (node (ref "D2") (pin "2") (pinfunction "K_2") (pintype "passive"))
      (node (ref "U1") (pin "1") (pinfunction "IN_1") (pintype "passive"))
      (node (ref "U2") (pin "1") (pinfunction "VIN_1") (pintype "passive"))
    )
    (net (code "73") (name "A3.3V") (class "Default")
      (node (ref "C12") (pin "1") (pinfunction "1_1") (pintype "passive"))
      (node (ref "C14") (pin "2") (pinfunction "2_2") (pintype "passive"))
      (node (ref "C27") (pin "2") (pinfunction "2_2") (pintype "passive"))
      (node (ref "C29") (pin "2") (pinfunction "2_2") (pintype "passive"))
      (node (ref "U4") (pin "2") (pinfunction "VOUT_2") (pintype "passive"))
      (node (ref "U5") (pin "21") (pinfunction "VREF+_21") (pintype "power_in"))
      (node (ref "U5") (pin "22") (pinfunction "VDDA_22") (pintype "power_in"))
      (node (ref "U7") (pin "12") (pinfunction "AVDD_12") (pintype "passive"))
    )
    (net (code "74") (name "AGND") (class "Default")
      (node (ref "C11") (pin "2") (pinfunction "2_2") (pintype "passive"))
      (node (ref "C12") (pin "2") (pinfunction "2_2") (pintype "passive"))
      (node (ref "C13") (pin "1") (pinfunction "1_1") (pintype "passive"))
      (node (ref "C14") (pin "1") (pinfunction "1_1") (pintype "passive"))
      (node (ref "C27") (pin "1") (pinfunction "1_1") (pintype "passive"))
      (node (ref "C28") (pin "1") (pinfunction "1_1") (pintype "passive"))
      (node (ref "C29") (pin "1") (pinfunction "1_1") (pintype "passive"))
      (node (ref "D11") (pin "1") (pinfunction "A_1") (pintype "passive"))
      (node (ref "D12") (pin "1") (pinfunction "A_1") (pintype "passive"))
      (node (ref "D13") (pin "1") (pinfunction "A_1") (pintype "passive"))
      (node (ref "D4") (pin "1") (pinfunction "A_1") (pintype "passive"))
      (node (ref "D5") (pin "1") (pinfunction "A_1") (pintype "passive"))
      (node (ref "D6") (pin "1") (pinfunction "A_1") (pintype "passive"))
      (node (ref "D7") (pin "1") (pinfunction "A_1") (pintype "passive"))
      (node (ref "D8") (pin "1") (pinfunction "A_1") (pintype "passive"))
      (node (ref "P3") (pin "2") (pinfunction "2_2") (pintype "passive"))
      (node (ref "P3") (pin "4") (pinfunction "4_4") (pintype "passive"))
      (node (ref "P3") (pin "6") (pinfunction "6_6") (pintype "passive"))
      (node (ref "P3") (pin "8") (pinfunction "8_8") (pintype "passive"))
      (node (ref "P4") (pin "2") (pinfunction "2_2") (pintype "passive"))
      (node (ref "P4") (pin "4") (pinfunction "4_4") (pintype "passive"))
      (node (ref "P4") (pin "6") (pinfunction "6_6") (pintype "passive"))
      (node (ref "P4") (pin "8") (pinfunction "8_8") (pintype "passive"))
      (node (ref "Q1") (pin "2") (pinfunction "S_2") (pintype "passive"))
      (node (ref "Q10") (pin "2") (pinfunction "S_2") (pintype "passive"))
      (node (ref "Q11") (pin "2") (pinfunction "S_2") (pintype "passive"))
      (node (ref "Q12") (pin "2") (pinfunction "S_2") (pintype "passive"))
      (node (ref "Q13") (pin "2") (pinfunction "S_2") (pintype "passive"))
      (node (ref "Q14") (pin "2") (pinfunction "S_2") (pintype "passive"))
      (node (ref "Q15") (pin "2") (pinfunction "S_2") (pintype "passive"))
      (node (ref "Q16") (pin "2") (pinfunction "S_2") (pintype "passive"))
      (node (ref "Q17") (pin "2") (pinfunction "S_2") (pintype "passive"))
      (node (ref "Q18") (pin "2") (pinfunction "S_2") (pintype "passive"))
      (node (ref "Q19") (pin "2") (pinfunction "S_2") (pintype "passive"))
      (node (ref "Q2") (pin "2") (pinfunction "S_2") (pintype "passive"))
      (node (ref "Q3") (pin "2") (pinfunction "S_2") (pintype "passive"))
      (node (ref "Q4") (pin "2") (pinfunction "S_2") (pintype "passive"))
      (node (ref "Q5") (pin "2") (pinfunction "S_2") (pintype "passive"))
      (node (ref "Q6") (pin "2") (pinfunction "S_2") (pintype "passive"))
      (node (ref "Q7") (pin "2") (pinfunction "S_2") (pintype "passive"))
      (node (ref "Q8") (pin "2") (pinfunction "S_2") (pintype "passive"))
      (node (ref "Q9") (pin "2") (pinfunction "S_2") (pintype "passive"))
      (node (ref "R1") (pin "2") (pinfunction "2_2") (pintype "passive"))
      (node (ref "U4") (pin "1") (pinfunction "VSS_1") (pintype "passive"))
      (node (ref "U5") (pin "19") (pinfunction "VSSA_19") (pintype "power_in"))
      (node (ref "U5") (pin "20") (pinfunction "VREF-_20") (pintype "power_in"))
      (node (ref "U6") (pin "7") (pinfunction "VEE_7") (pintype "passive"))
      (node (ref "U7") (pin "5") (pinfunction "AVSS_5") (pintype "passive"))
      (node (ref "U9") (pin "7") (pinfunction "VEE_7") (pintype "passive"))
    )
    (net (code "75") (name "GND") (class "Default")
      (node (ref "C1") (pin "2") (pinfunction "2_2") (pintype "passive"))
      (node (ref "C10") (pin "1") (pinfunction "1_1") (pintype "passive"))
      (node (ref "C2") (pin "2") (pinfunction "2_2") (pintype "passive"))
      (node (ref "C21") (pin "1") (pinfunction "1_1") (pintype "passive"))
      (node (ref "C23") (pin "1") (pinfunction "1_1") (pintype "passive"))
      (node (ref "C24") (pin "1") (pinfunction "1_1") (pintype "passive"))
      (node (ref "C26") (pin "1") (pinfunction "1_1") (pintype "passive"))
      (node (ref "C3") (pin "1") (pinfunction "1_1") (pintype "passive"))
      (node (ref "C30") (pin "1") (pinfunction "1_1") (pintype "passive"))
      (node (ref "C31") (pin "1") (pinfunction "1_1") (pintype "passive"))
      (node (ref "C32") (pin "1") (pinfunction "1_1") (pintype "passive"))
      (node (ref "C33") (pin "1") (pinfunction "1_1") (pintype "passive"))
      (node (ref "C34") (pin "1") (pinfunction "1_1") (pintype "passive"))
      (node (ref "C35") (pin "1") (pinfunction "1_1") (pintype "passive"))
      (node (ref "C36") (pin "1") (pinfunction "1_1") (pintype "passive"))
      (node (ref "C4") (pin "1") (pinfunction "1_1") (pintype "passive"))
      (node (ref "C6") (pin "2") (pinfunction "2_2") (pintype "passive"))
      (node (ref "C7") (pin "2") (pinfunction "2_2") (pintype "passive"))
      (node (ref "C8") (pin "1") (pinfunction "1_1") (pintype "passive"))
      (node (ref "C9") (pin "1") (pinfunction "1_1") (pintype "passive"))
      (node (ref "D14") (pin "1") (pinfunction "A_1") (pintype "passive"))
      (node (ref "D15") (pin "1") (pinfunction "A_1") (pintype "passive"))
      (node (ref "D16") (pin "1") (pinfunction "A_1") (pintype "passive"))
      (node (ref "D2") (pin "1") (pinfunction "A_1") (pintype "passive"))
      (node (ref "D3") (pin "1") (pinfunction "A_1") (pintype "passive"))
      (node (ref "P1") (pin "5") (pinfunction "5_5") (pintype "passive"))
      (node (ref "P2") (pin "1") (pinfunction "1_1") (pintype "passive"))
      (node (ref "P5") (pin "3") (pinfunction "3_3") (pintype "passive"))
      (node (ref "R1") (pin "1") (pinfunction "1_1") (pintype "passive"))
      (node (ref "R35") (pin "2") (pinfunction "2_2") (pintype "passive"))
      (node (ref "R36") (pin "2") (pinfunction "2_2") (pintype "passive"))
      (node (ref "S1") (pin "10") (pinfunction "10_10") (pintype "passive"))
      (node (ref "S1") (pin "11") (pinfunction "11_11") (pintype "passive"))
      (node (ref "S1") (pin "12") (pinfunction "12_12") (pintype "passive"))
      (node (ref "S1") (pin "13") (pinfunction "13_13") (pintype "passive"))
      (node (ref "S1") (pin "14") (pinfunction "14_14") (pintype "passive"))
      (node (ref "S1") (pin "15") (pinfunction "15_15") (pintype "passive"))
      (node (ref "S1") (pin "16") (pinfunction "16_16") (pintype "passive"))
      (node (ref "S1") (pin "9") (pinfunction "9_9") (pintype "passive"))
      (node (ref "U1") (pin "2") (pinfunction "GND_2") (pintype "passive"))
      (node (ref "U10") (pin "5") (pinfunction "5B_5") (pintype "passive"))
      (node (ref "U10") (pin "6") (pinfunction "6B_6") (pintype "passive"))
      (node (ref "U10") (pin "7") (pinfunction "7B_7") (pintype "passive"))
      (node (ref "U10") (pin "8") (pinfunction "E_8") (pintype "passive"))
      (node (ref "U2") (pin "4") (pinfunction "ON/OFF_4") (pintype "passive"))
      (node (ref "U2") (pin "5") (pinfunction "GND_5") (pintype "passive"))
      (node (ref "U2") (pin "6") (pinfunction "GND_6") (pintype "passive"))
      (node (ref "U2") (pin "7") (pinfunction "GND_7") (pintype "passive"))
      (node (ref "U2") (pin "8") (pinfunction "GND_8") (pintype "passive"))
      (node (ref "U3") (pin "1") (pinfunction "VSS_1") (pintype "passive"))
      (node (ref "U5") (pin "10") (pinfunction "VSS_5_10") (pintype "power_in"))
      (node (ref "U5") (pin "27") (pinfunction "VSS_4_27") (pintype "power_in"))
      (node (ref "U5") (pin "49") (pinfunction "VSS_1_49") (pintype "power_in"))
      (node (ref "U5") (pin "74") (pinfunction "VSS_2_74") (pintype "power_in"))
      (node (ref "U5") (pin "99") (pinfunction "VSS_3_99") (pintype "power_in"))
      (node (ref "U6") (pin "8") (pinfunction "VSS_8") (pintype "passive"))
      (node (ref "U7") (pin "3") (pinfunction "CLK_3") (pintype "passive"))
      (node (ref "U7") (pin "4") (pinfunction "DGND_4") (pintype "passive"))
      (node (ref "U8") (pin "2") (pinfunction "GND_2") (pintype "passive"))
      (node (ref "U8") (pin "8") (pinfunction "S_8") (pintype "passive"))
      (node (ref "U9") (pin "8") (pinfunction "VSS_8") (pintype "passive"))
    )
    (net (code "76") (name "Net-(D1-A)") (class "Default")
      (node (ref "D1") (pin "1") (pinfunction "A_1") (pintype "passive"))
      (node (ref "F1") (pin "2") (pinfunction "2_2") (pintype "passive"))
    )
    (net (code "77") (name "Net-(D9-K)") (class "Default")
      (node (ref "D9") (pin "2") (pinfunction "K_2") (pintype "passive"))
      (node (ref "R29") (pin "2") (pinfunction "2_2") (pintype "passive"))
    )
    (net (code "78") (name "Net-(D10-K)") (class "Default")
      (node (ref "D10") (pin "2") (pinfunction "K_2") (pintype "passive"))
      (node (ref "R30") (pin "2") (pinfunction "2_2") (pintype "passive"))
    )
    (net (code "79") (name "Net-(D16-K)") (class "Default")
      (node (ref "D16") (pin "2") (pinfunction "K_2") (pintype "passive"))
      (node (ref "L1") (pin "1") (pinfunction "1_1") (pintype "passive"))
      (node (ref "U2") (pin "2") (pinfunction "OUTPUT_2") (pintype "passive"))
    )
    (net (code "80") (name "Net-(Q1-D)") (class "Default")
      (node (ref "Q1") (pin "3") (pinfunction "D_3") (pintype "passive"))
      (node (ref "R5") (pin "1") (pinfunction "1_1") (pintype "passive"))
      (node (ref "R6") (pin "1") (pinfunction "1_1") (pintype "passive"))
    )
    (net (code "81") (name "Net-(Q2-D)") (class "Default")
      (node (ref "C15") (pin "1") (pinfunction "1_1") (pintype "passive"))
      (node (ref "Q2") (pin "3") (pinfunction "D_3") (pintype "passive"))
      (node (ref "R8") (pin "1") (pinfunction "1_1") (pintype "passive"))
    )
    (net (code "82") (name "Net-(Q3-D)") (class "Default")
      (node (ref "Q3") (pin "3") (pinfunction "D_3") (pintype "passive"))
      (node (ref "R10") (pin "1") (pinfunction "1_1") (pintype "passive"))
      (node (ref "R9") (pin "1") (pinfunction "1_1") (pintype "passive"))
    )
    (net (code "83") (name "Net-(Q4-D)") (class "Default")
      (node (ref "C16") (pin "1") (pinfunction "1_1") (pintype "passive"))
      (node (ref "Q4") (pin "3") (pinfunction "D_3") (pintype "passive"))
      (node (ref "R12") (pin "1") (pinfunction "1_1") (pintype "passive"))
    )
    (net (code "84") (name "Net-(Q5-D)") (class "Default")
      (node (ref "Q5") (pin "3") (pinfunction "D_3") (pintype "passive"))
      (node (ref "R13") (pin "1") (pinfunction "1_1") (pintype "passive"))
      (node (ref "R14") (pin "1") (pinfunction "1_1") (pintype "passive"))
    )
    (net (code "85") (name "Net-(Q6-D)") (class "Default")
      (node (ref "C17") (pin "1") (pinfunction "1_1") (pintype "passive"))
      (node (ref "Q6") (pin "3") (pinfunction "D_3") (pintype "passive"))
      (node (ref "R16") (pin "1") (pinfunction "1_1") (pintype "passive"))
    )
    (net (code "86") (name "Net-(Q7-D)") (class "Default")
      (node (ref "Q7") (pin "3") (pinfunction "D_3") (pintype "passive"))
      (node (ref "R17") (pin "1") (pinfunction "1_1") (pintype "passive"))
      (node (ref "R18") (pin "1") (pinfunction "1_1") (pintype "passive"))
    )
    (net (code "87") (name "Net-(Q8-D)") (class "Default")
      (node (ref "C18") (pin "1") (pinfunction "1_1") (pintype "passive"))
      (node (ref "Q8") (pin "3") (pinfunction "D_3") (pintype "passive"))
      (node (ref "R20") (pin "1") (pinfunction "1_1") (pintype "passive"))
    )
    (net (code "88") (name "Net-(Q9-D)") (class "Default")
      (node (ref "Q9") (pin "3") (pinfunction "D_3") (pintype "passive"))
      (node (ref "R21") (pin "1") (pinfunction "1_1") (pintype "passive"))
      (node (ref "R22") (pin "1") (pinfunction "1_1") (pintype "passive"))
    )
    (net (code "89") (name "Net-(Q10-D)") (class "Default")
      (node (ref "C19") (pin "1") (pinfunction "1_1") (pintype "passive"))
      (node (ref "Q10") (pin "3") (pinfunction "D_3") (pintype "passive"))
      (node (ref "R24") (pin "1") (pinfunction "1_1") (pintype "passive"))
    )
    (net (code "90") (name "Net-(Q11-D)") (class "Default")
      (node (ref "Q11") (pin "3") (pinfunction "D_3") (pintype "passive"))
      (node (ref "R25") (pin "1") (pinfunction "1_1") (pintype "passive"))
      (node (ref "R26") (pin "1") (pinfunction "1_1") (pintype "passive"))
    )
    (net (code "91") (name "Net-(Q12-D)") (class "Default")
      (node (ref "C20") (pin "1") (pinfunction "1_1") (pintype "passive"))
      (node (ref "Q12") (pin "3") (pinfunction "D_3") (pintype "passive"))
      (node (ref "R28") (pin "1") (pinfunction "1_1") (pintype "passive"))
    )
    (net (code "92") (name "Net-(Q13-D)") (class "Default")
      (node (ref "Q13") (pin "3") (pinfunction "D_3") (pintype "passive"))
      (node (ref "R31") (pin "1") (pinfunction "1_1") (pintype "passive"))
      (node (ref "R32") (pin "1") (pinfunction "1_1") (pintype "passive"))
    )
    (net (code "93") (name "Net-(Q14-D)") (class "Default")
      (node (ref "C22") (pin "1") (pinfunction "1_1") (pintype "passive"))
      (node (ref "Q14") (pin "3") (pinfunction "D_3") (pintype "passive"))
      (node (ref "R34") (pin "1") (pinfunction "1_1") (pintype "passive"))
    )
    (net (code "94") (name "Net-(Q15-D)") (class "Default")
      (node (ref "Q15") (pin "3") (pinfunction "D_3") (pintype "passive"))
      (node (ref "R37") (pin "1") (pinfunction "1_1") (pintype "passive"))
      (node (ref "R38") (pin "1") (pinfunction "1_1") (pintype "passive"))
    )
    (net (code "95") (name "Net-(Q16-D)") (class "Default")
      (node (ref "C25") (pin "1") (pinfunction "1_1") (pintype "passive"))
      (node (ref "Q16") (pin "3") (pinfunction "D_3") (pintype "passive"))
      (node (ref "R40") (pin "1") (pinfunction "1_1") (pintype "passive"))
    )
    (net (code "96") (name "Net-(Q17-D)") (class "Default")
      (node (ref "Q17") (pin "3") (pinfunction "D_3") (pintype "passive"))
      (node (ref "R41") (pin "1") (pinfunction "1_1") (pintype "passive"))
    )
    (net (code "97") (name "Net-(Q18-D)") (class "Default")
      (node (ref "Q18") (pin "3") (pinfunction "D_3") (pintype "passive"))
      (node (ref "R42") (pin "1") (pinfunction "1_1") (pintype "passive"))
    )
    (net (code "98") (name "Net-(Q19-D)") (class "Default")
      (node (ref "Q19") (pin "3") (pinfunction "D_3") (pintype "passive"))
      (node (ref "R43") (pin "1") (pinfunction "1_1") (pintype "passive"))
    )
    (net (code "99") (name "Net-(U4-VIN)") (class "Default")
      (node (ref "C11") (pin "1") (pinfunction "1_1") (pintype "passive"))
      (node (ref "C13") (pin "2") (pinfunction "2_2") (pintype "passive"))
      (node (ref "I2") (pin "1") (pinfunction "1_1") (pintype "passive"))
      (node (ref "U4") (pin "3") (pinfunction "VIN_3") (pintype "passive"))
    )
    (net (code "100") (name "Net-(U5-BOOT0)") (class "Default")
      (node (ref "R35") (pin "1") (pinfunction "1_1") (pintype "passive"))
      (node (ref "U5") (pin "94") (pinfunction "BOOT0_94") (pintype "input"))
    )
    (net (code "101") (name "Net-(U5-OSC_IN)") (class "Default")
      (node (ref "C23") (pin "2") (pinfunction "2_2") (pintype "passive"))
      (node (ref "U5") (pin "12") (pinfunction "OSC_IN_12") (pintype "input"))
      (node (ref "Y1") (pin "2") (pinfunction "OSC2_2") (pintype "passive"))
    )
    (net (code "102") (name "Net-(U5-OSC_OUT)") (class "Default")
      (node (ref "C24") (pin "2") (pinfunction "2_2") (pintype "passive"))
      (node (ref "U5") (pin "13") (pinfunction "OSC_OUT_13") (pintype "output"))
      (node (ref "Y1") (pin "1") (pinfunction "OSC1_1") (pintype "passive"))
    )
    (net (code "103") (name "Net-(U5-PB2)") (class "Default")
      (node (ref "R36") (pin "1") (pinfunction "1_1") (pintype "passive"))
      (node (ref "U5") (pin "37") (pinfunction "PB2_37") (pintype "bidirectional"))
    )
    (net (code "104") (name "Net-(U7-AIN1)") (class "Default")
      (node (ref "R41") (pin "2") (pinfunction "2_2") (pintype "passive"))
      (node (ref "R42") (pin "2") (pinfunction "2_2") (pintype "passive"))
      (node (ref "R43") (pin "2") (pinfunction "2_2") (pintype "passive"))
      (node (ref "U7") (pin "10") (pinfunction "AIN1_10") (pintype "passive"))
    )
    (net (code "105") (name "VCC") (class "Default")
      (node (ref "F1") (pin "1") (pinfunction "1_1") (pintype "passive"))
      (node (ref "P1") (pin "1") (pinfunction "1_1") (pintype "passive"))
      (node (ref "P2") (pin "5") (pinfunction "5_5") (pintype "passive"))
    )
    (net (code "106") (name "unconnected-(U5-NC-Pad73)") (class "Default")
      (node (ref "U5") (pin "73") (pinfunction "NC_73") (pintype "passive"))
    )
    (net (code "107") (name "unconnected-(U5-PA8-Pad67)") (class "Default")
      (node (ref "U5") (pin "67") (pinfunction "PA8_67") (pintype "bidirectional"))
    )
    (net (code "108") (name "unconnected-(U5-PA9-Pad68)") (class "Default")
      (node (ref "U5") (pin "68") (pinfunction "PA9_68") (pintype "bidirectional"))
    )
    (net (code "109") (name "unconnected-(U5-PA10-Pad69)") (class "Default")
      (node (ref "U5") (pin "69") (pinfunction "PA10_69") (pintype "bidirectional"))
    )
    (net (code "110") (name "unconnected-(U5-PB3-Pad89)") (class "Default")
      (node (ref "U5") (pin "89") (pinfunction "PB3_89") (pintype "bidirectional"))
    )
    (net (code "111") (name "unconnected-(U5-PB4-Pad90)") (class "Default")
      (node (ref "U5") (pin "90") (pinfunction "PB4_90") (pintype "bidirectional"))
    )
    (net (code "112") (name "unconnected-(U5-PB5-Pad91)") (class "Default")
      (node (ref "U5") (pin "91") (pinfunction "PB5_91") (pintype "bidirectional"))
    )
    (net (code "113") (name "unconnected-(U5-PB6-Pad92)") (class "Default")
      (node (ref "U5") (pin "92") (pinfunction "PB6_92") (pintype "bidirectional"))
    )
    (net (code "114") (name "unconnected-(U5-PB7-Pad93)") (class "Default")
      (node (ref "U5") (pin "93") (pinfunction "PB7_93") (pintype "bidirectional"))
    )
    (net (code "115") (name "unconnected-(U5-PB8-Pad95)") (class "Default")
      (node (ref "U5") (pin "95") (pinfunction "PB8_95") (pintype "bidirectional"))
    )
    (net (code "116") (name "unconnected-(U5-PB9-Pad96)") (class "Default")
      (node (ref "U5") (pin "96") (pinfunction "PB9_96") (pintype "bidirectional"))
    )
    (net (code "117") (name "unconnected-(U5-PC6-Pad63)") (class "Default")
      (node (ref "U5") (pin "63") (pinfunction "PC6_63") (pintype "bidirectional"))
    )
    (net (code "118") (name "unconnected-(U5-PC7-Pad64)") (class "Default")
      (node (ref "U5") (pin "64") (pinfunction "PC7_64") (pintype "bidirectional"))
    )
    (net (code "119") (name "unconnected-(U5-PC8-Pad65)") (class "Default")
      (node (ref "U5") (pin "65") (pinfunction "PC8_65") (pintype "bidirectional"))
    )
    (net (code "120") (name "unconnected-(U5-PC9-Pad66)") (class "Default")
      (node (ref "U5") (pin "66") (pinfunction "PC9_66") (pintype "bidirectional"))
    )
    (net (code "121") (name "unconnected-(U5-PC13-TAMPER-RTC-Pad7)") (class "Default")
      (node (ref "U5") (pin "7") (pinfunction "PC13-TAMPER-RTC_7") (pintype "bidirectional"))
    )
    (net (code "122") (name "unconnected-(U5-PC14-OSC32_IN-Pad8)") (class "Default")
      (node (ref "U5") (pin "8") (pinfunction "PC14-OSC32_IN_8") (pintype "bidirectional"))
    )
    (net (code "123") (name "unconnected-(U5-PC15-OSC32_OUT-Pad9)") (class "Default")
      (node (ref "U5") (pin "9") (pinfunction "PC15-OSC32_OUT_9") (pintype "bidirectional"))
    )
    (net (code "124") (name "unconnected-(U5-PD6-Pad87)") (class "Default")
      (node (ref "U5") (pin "87") (pinfunction "PD6_87") (pintype "bidirectional"))
    )
    (net (code "125") (name "unconnected-(U5-PD7-Pad88)") (class "Default")
      (node (ref "U5") (pin "88") (pinfunction "PD7_88") (pintype "bidirectional"))
    )
    (net (code "126") (name "unconnected-(U5-PD10-Pad57)") (class "Default")
      (node (ref "U5") (pin "57") (pinfunction "PD10_57") (pintype "bidirectional"))
    )
    (net (code "127") (name "unconnected-(U5-PD11-Pad58)") (class "Default")
      (node (ref "U5") (pin "58") (pinfunction "PD11_58") (pintype "bidirectional"))
    )
    (net (code "128") (name "unconnected-(U5-PD12-Pad59)") (class "Default")
      (node (ref "U5") (pin "59") (pinfunction "PD12_59") (pintype "bidirectional"))
    )
    (net (code "129") (name "unconnected-(U5-PD13-Pad60)") (class "Default")
      (node (ref "U5") (pin "60") (pinfunction "PD13_60") (pintype "bidirectional"))
    )
    (net (code "130") (name "unconnected-(U5-PD14-Pad61)") (class "Default")
      (node (ref "U5") (pin "61") (pinfunction "PD14_61") (pintype "bidirectional"))
    )
    (net (code "131") (name "unconnected-(U5-PD15-Pad62)") (class "Default")
      (node (ref "U5") (pin "62") (pinfunction "PD15_62") (pintype "bidirectional"))
    )
    (net (code "132") (name "unconnected-(U5-PE0-Pad97)") (class "Default")
      (node (ref "U5") (pin "97") (pinfunction "PE0_97") (pintype "bidirectional"))
    )
    (net (code "133") (name "unconnected-(U5-PE1-Pad98)") (class "Default")
      (node (ref "U5") (pin "98") (pinfunction "PE1_98") (pintype "bidirectional"))
    )
    (net (code "134") (name "unconnected-(U5-PE5-Pad4)") (class "Default")
      (node (ref "U5") (pin "4") (pinfunction "PE5_4") (pintype "bidirectional"))
    )
    (net (code "135") (name "unconnected-(U5-PE6-Pad5)") (class "Default")
      (node (ref "U5") (pin "5") (pinfunction "PE6_5") (pintype "bidirectional"))
    )
    (net (code "136") (name "unconnected-(U7-AIN2-Pad7)") (class "Default")
      (node (ref "U7") (pin "7") (pinfunction "AIN2_7") (pintype "passive"))
    )
    (net (code "137") (name "unconnected-(U7-AIN3{slash}REFN1-Pad6)") (class "Default")
      (node (ref "U7") (pin "6") (pinfunction "AIN3/REFN1_6") (pintype "passive"))
    )
    (net (code "138") (name "unconnected-(U7-REFN0-Pad8)") (class "Default")
      (node (ref "U7") (pin "8") (pinfunction "REFN0_8") (pintype "passive"))
    )
    (net (code "139") (name "unconnected-(U10-5C-Pad12)") (class "Default")
      (node (ref "U10") (pin "12") (pinfunction "5C_12") (pintype "passive"))
    )
    (net (code "140") (name "unconnected-(U10-6C-Pad11)") (class "Default")
      (node (ref "U10") (pin "11") (pinfunction "6C_11") (pintype "passive"))
    )
    (net (code "141") (name "unconnected-(U10-7C-Pad10)") (class "Default")
      (node (ref "U10") (pin "10") (pinfunction "7C_10") (pintype "passive"))
    )
  )
)
